# Maker_Display2.net
KiCad netlist of a schematic drawn in EAGLE
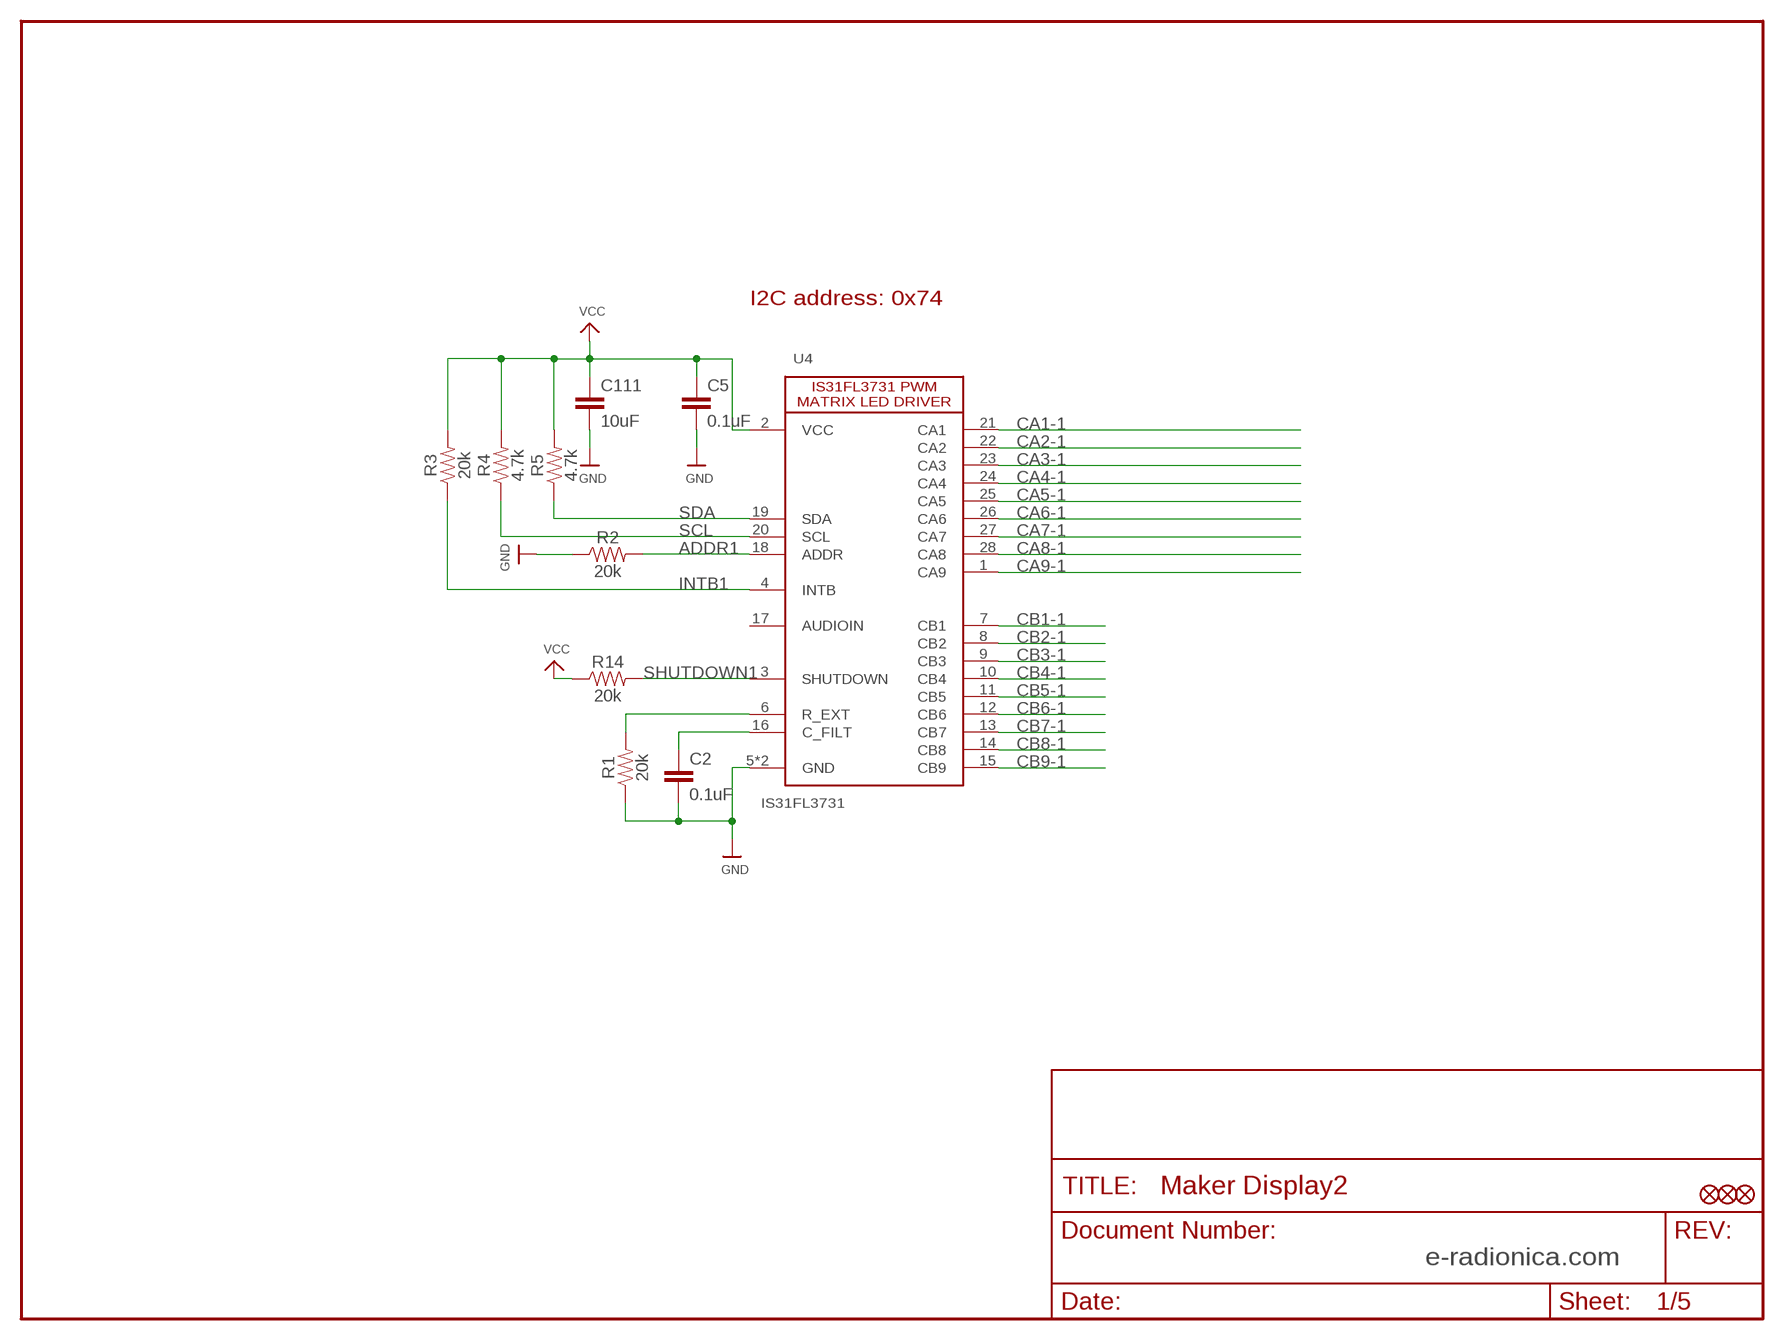
[diagram p0: schematic, sheet 1]
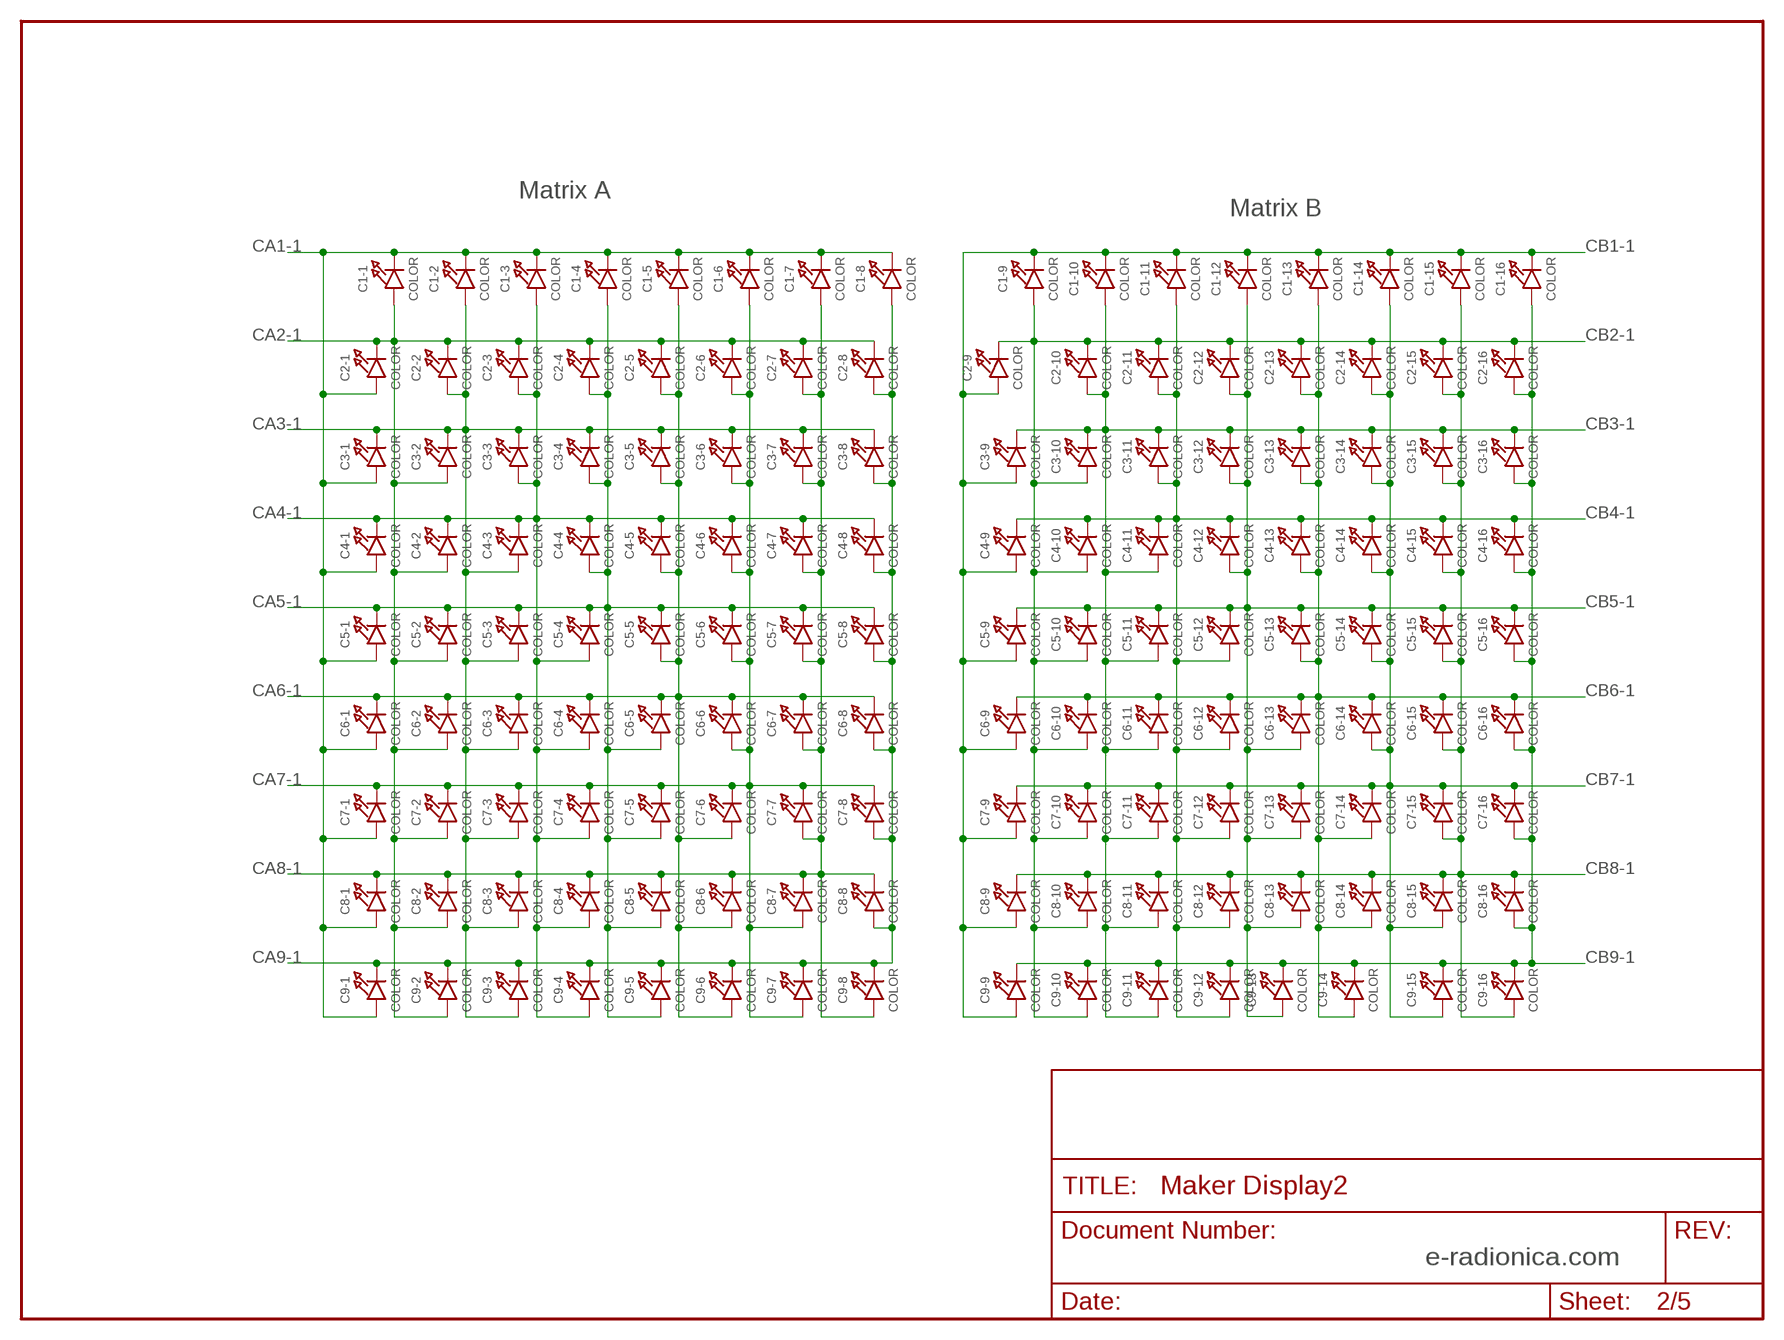
[diagram p1: schematic, sheet 2]
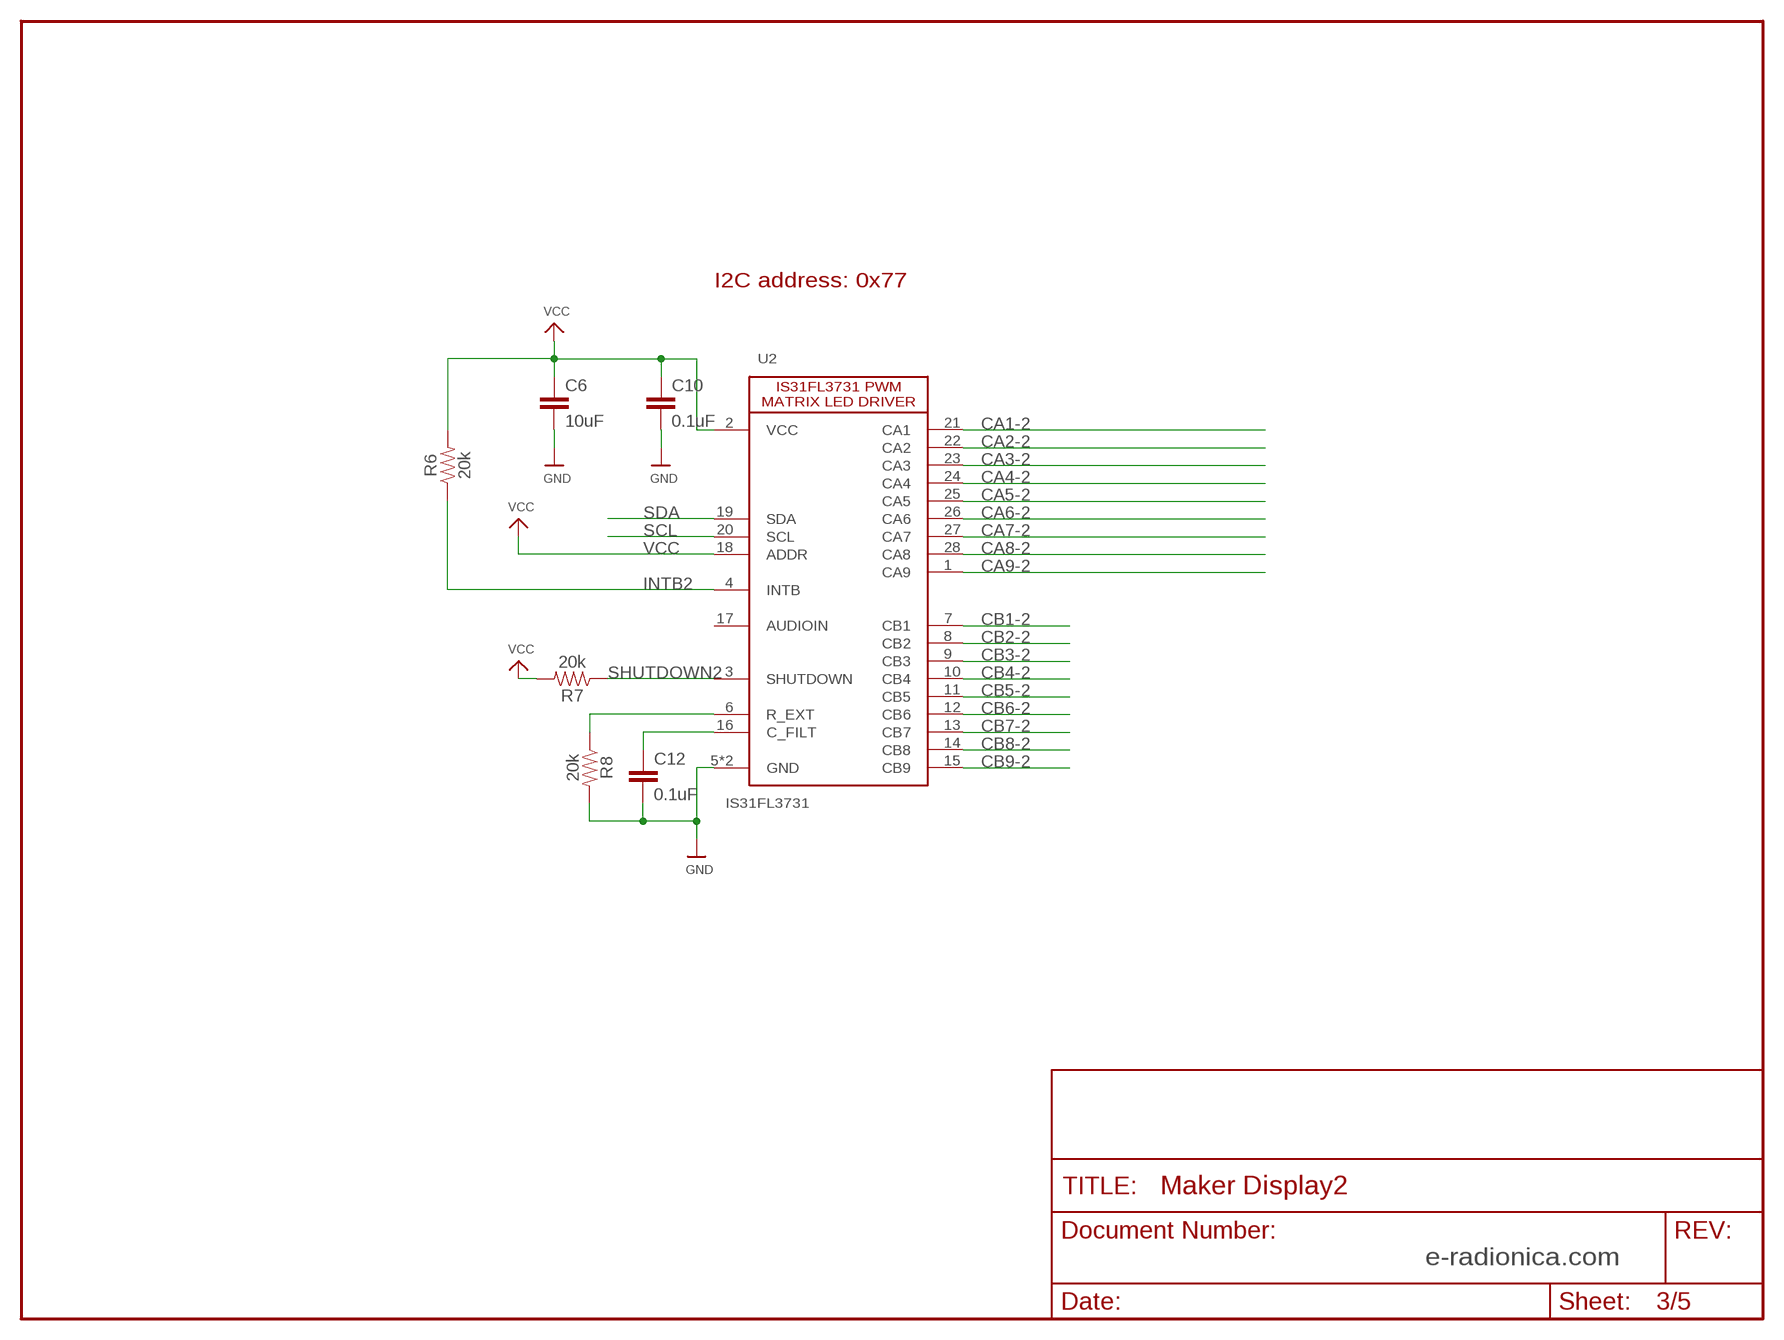
[diagram p2: schematic, sheet 3]
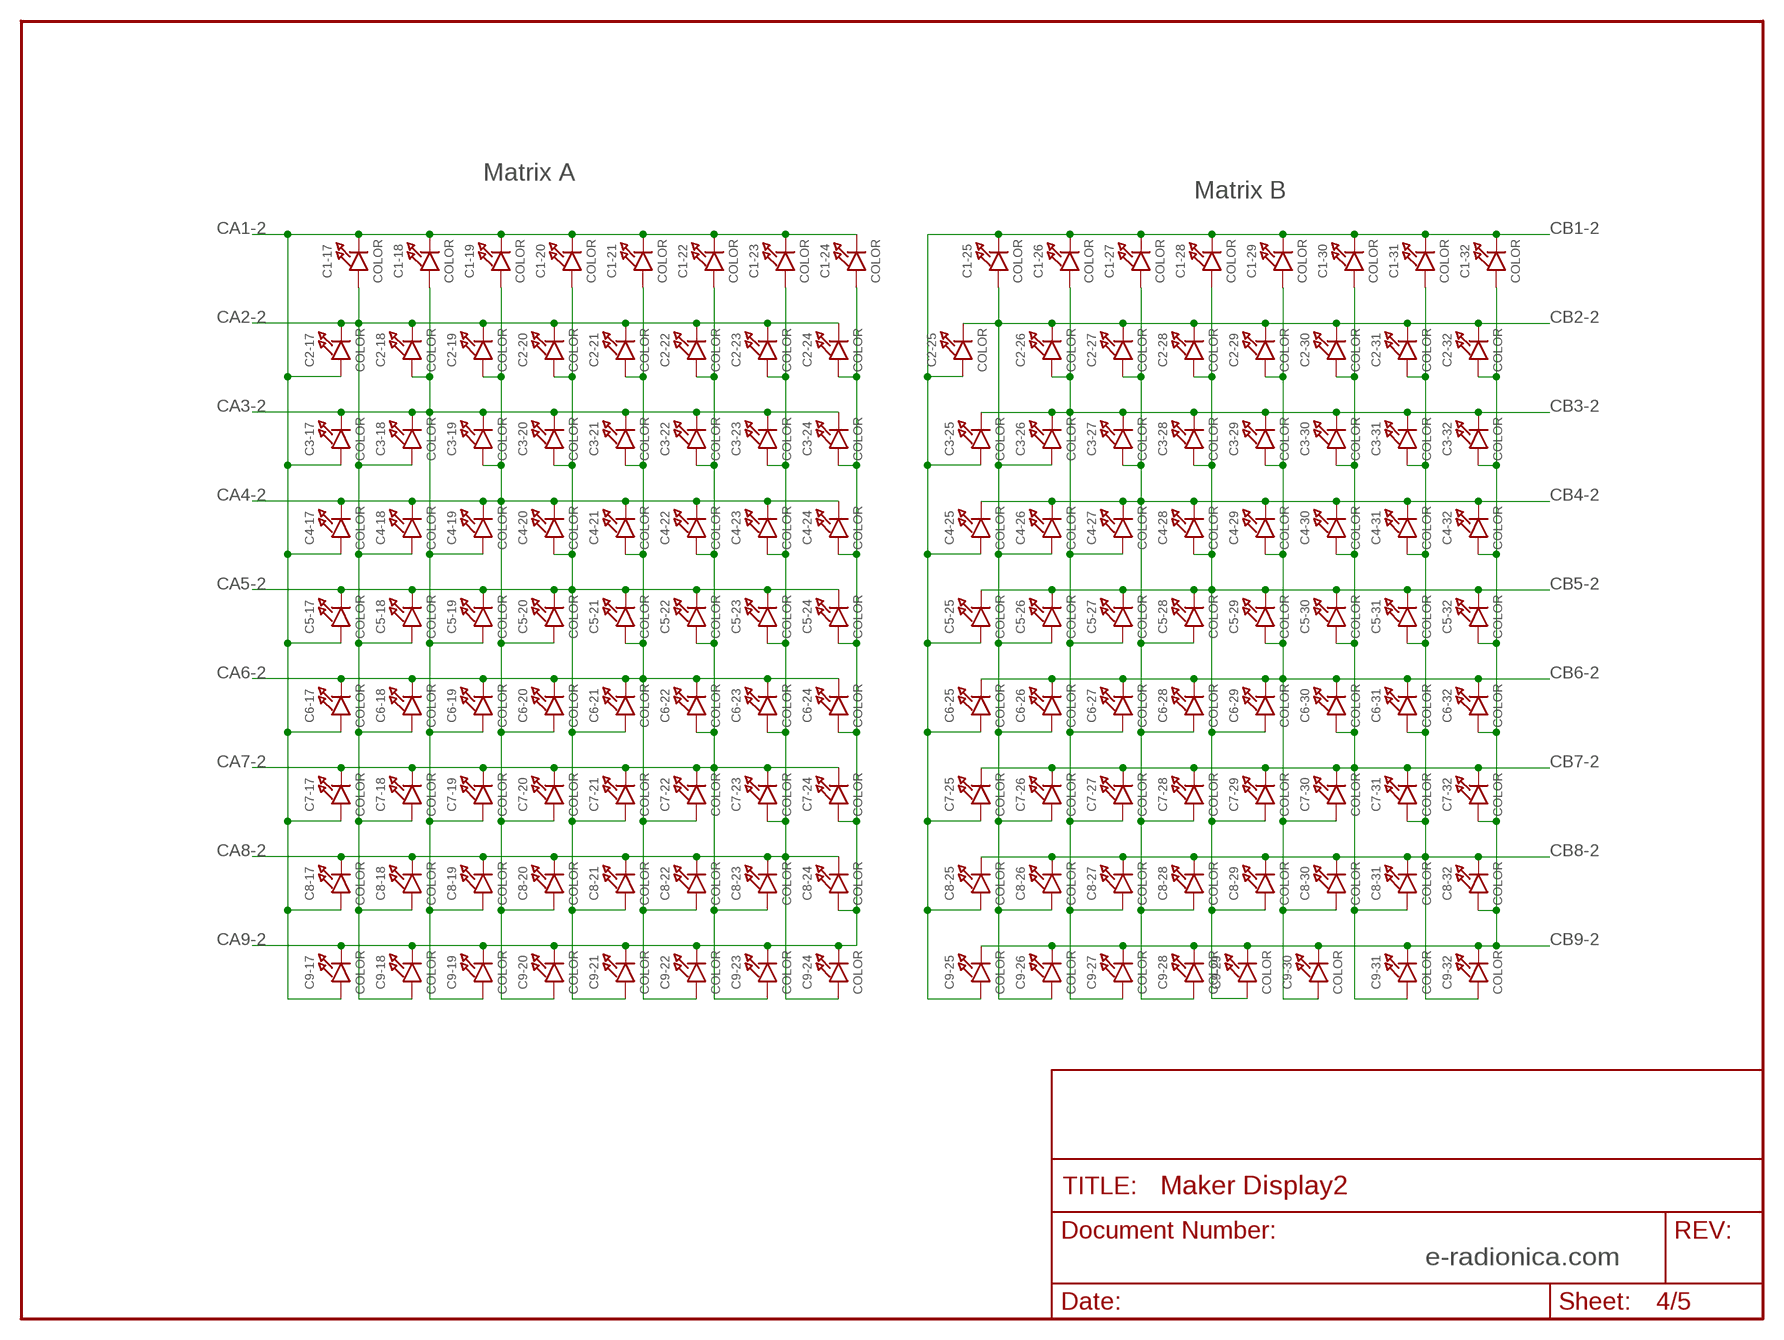
[diagram p3: schematic, sheet 4]
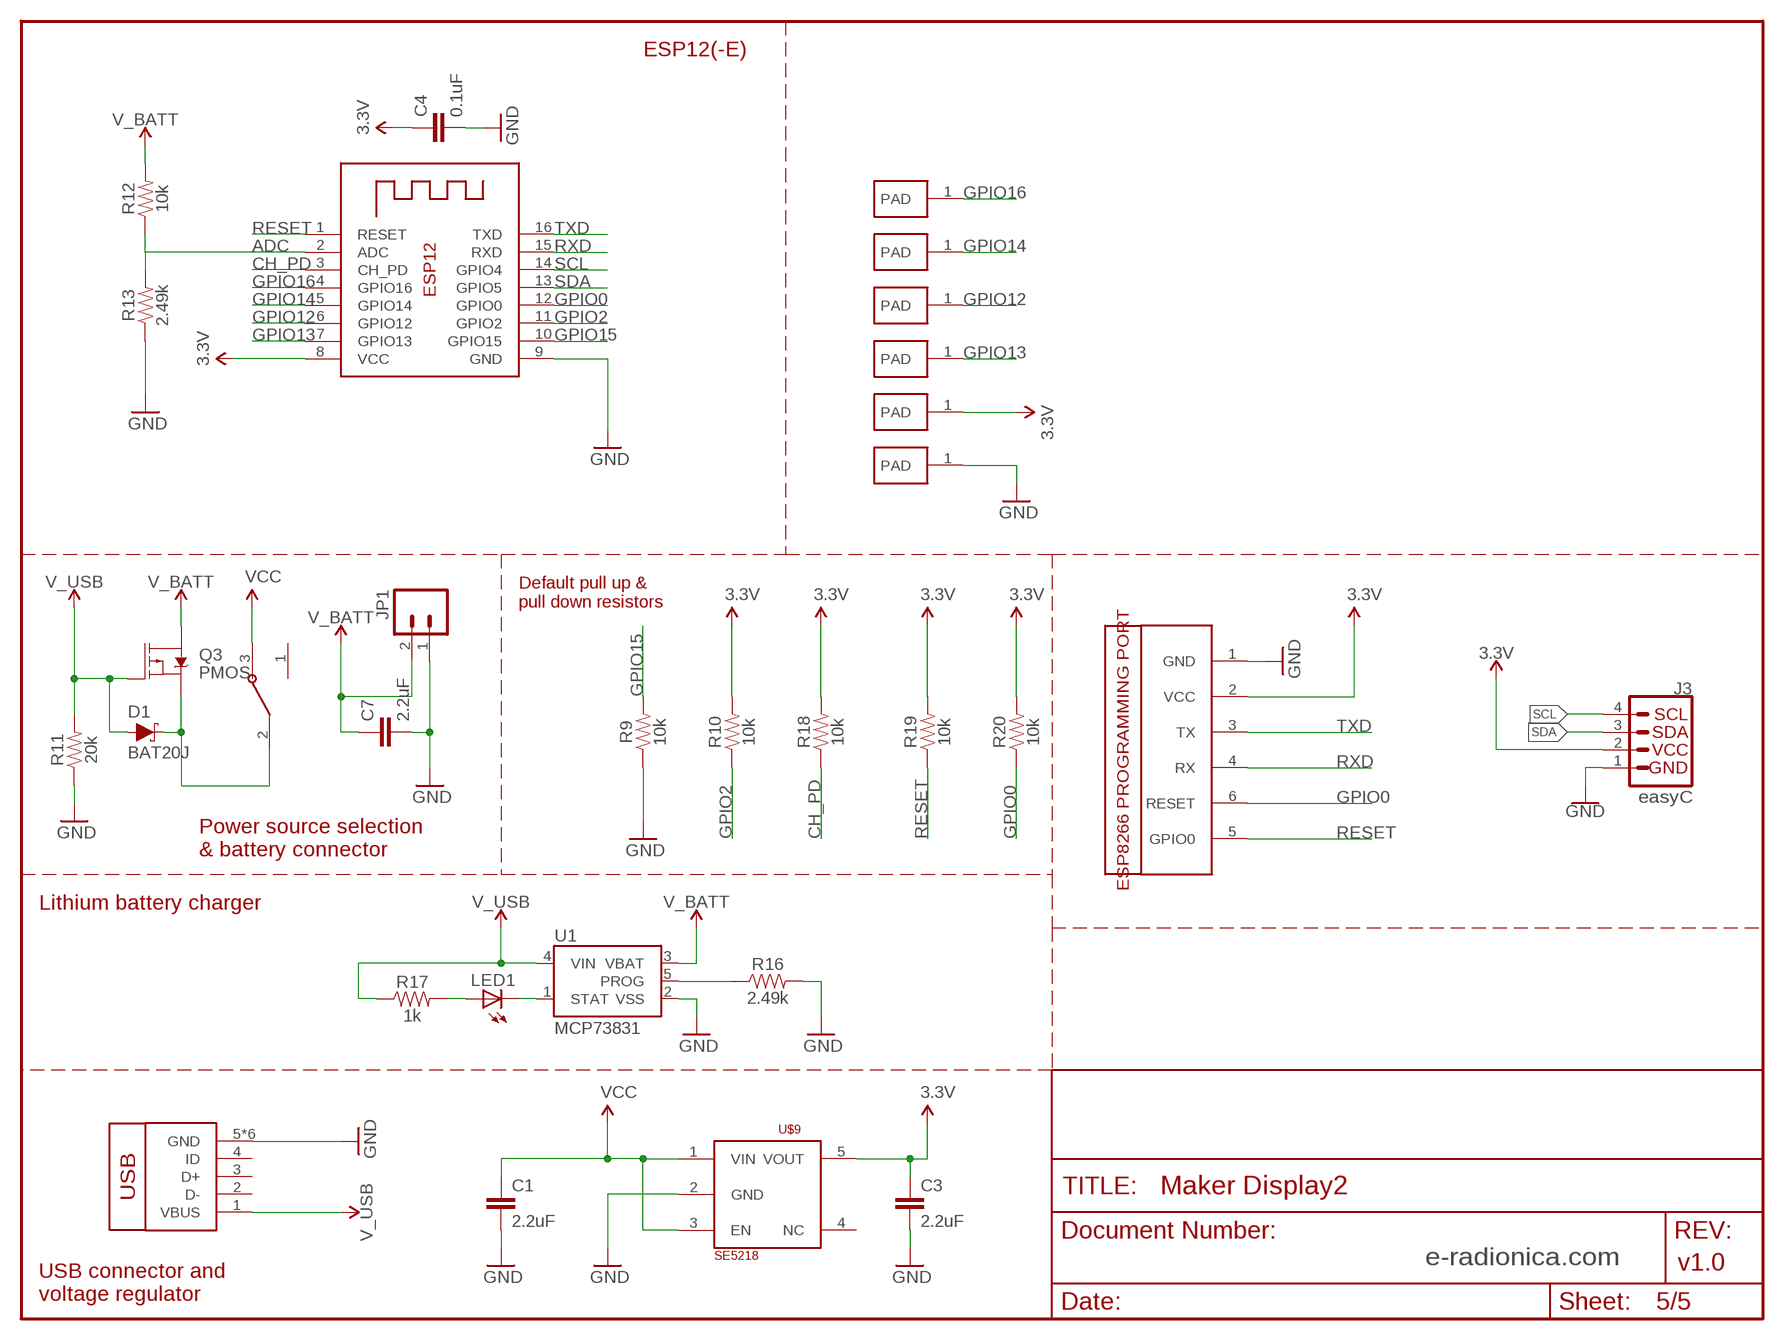
[diagram p4: schematic, sheet 5]

(export (version "E")
  (design (tool "Eeschema 10.0.6"))
  (components
    (comp (ref "C1")
      (value "2.2uF")
      (footprint "eagle-import:0603")
      (libsource (lib "eagle-import") (part "2.2UF-0603-10V-20%"))
    )
    (comp (ref "C3")
      (value "2.2uF")
      (footprint "eagle-import:0603")
      (libsource (lib "eagle-import") (part "2.2UF-0603-10V-20%"))
    )
    (comp (ref "C4")
      (value "0.1uF")
      (footprint "eagle-import:0603")
      (libsource (lib "eagle-import") (part "0.1UF-0603-25V-(+80/-20%)"))
    )
    (comp (ref "C7")
      (value "2.2uF")
      (footprint "eagle-import:0603")
      (libsource (lib "eagle-import") (part "2.2UF-0603-10V-20%"))
    )
    (comp (ref "D1")
      (value "BAT20J")
      (footprint "eagle-import:SOD-323")
      (libsource (lib "eagle-import") (part "DIODE-SCHOTTKY-BAT20J"))
    )
    (comp (ref "J3")
      (value "QWIIC_CONNECTORJS-1MM")
      (footprint "eagle-import:1X04_1MM_RA")
      (libsource (lib "eagle-import") (part "QWIIC_CONNECTORJS-1MM"))
    )
    (comp (ref "JP1")
      (value "M02-JST-2MM-SMT")
      (footprint "eagle-import:JST-2-SMD")
      (libsource (lib "eagle-import") (part "M02-JST-2MM-SMT"))
    )
    (comp (ref "LED1")
      (value "LEDCHIPLED_0805")
      (footprint "eagle-import:CHIPLED_0805")
      (libsource (lib "eagle-import") (part "LEDCHIPLED_0805"))
    )
    (comp (ref "Q3")
      (value "PMOS")
      (footprint "eagle-import:SOT23-3")
      (libsource (lib "eagle-import") (part "MOSFET_PCH-DMG2307L"))
    )
    (comp (ref "R9")
      (value "10k")
      (footprint "eagle-import:0603")
      (libsource (lib "eagle-import") (part "10KOHM-0603-1/10W-1%"))
    )
    (comp (ref "R10")
      (value "10k")
      (footprint "eagle-import:0603")
      (libsource (lib "eagle-import") (part "10KOHM-0603-1/10W-1%"))
    )
    (comp (ref "R11")
      (value "20k")
      (footprint "eagle-import:0603")
      (libsource (lib "eagle-import") (part "20KOHM-0603-1/10W-1%"))
    )
    (comp (ref "R12")
      (value "10k")
      (footprint "eagle-import:0603")
      (libsource (lib "eagle-import") (part "10KOHM-0603-1/10W-1%"))
    )
    (comp (ref "R13")
      (value "2.49k")
      (footprint "eagle-import:0603")
      (libsource (lib "eagle-import") (part "2.49KOHM-0603-1/10W-1%"))
    )
    (comp (ref "R16")
      (value "2.49k")
      (footprint "eagle-import:0603")
      (libsource (lib "eagle-import") (part "2.49KOHM-0603-1/10W-1%"))
    )
    (comp (ref "R17")
      (value "1k")
      (footprint "eagle-import:0603")
      (libsource (lib "eagle-import") (part "1KOHM-0603-1/10W-1%"))
    )
    (comp (ref "R18")
      (value "10k")
      (footprint "eagle-import:0603")
      (libsource (lib "eagle-import") (part "10KOHM-0603-1/10W-1%"))
    )
    (comp (ref "R19")
      (value "10k")
      (footprint "eagle-import:0603")
      (libsource (lib "eagle-import") (part "10KOHM-0603-1/10W-1%"))
    )
    (comp (ref "R20")
      (value "10k")
      (footprint "eagle-import:0603")
      (libsource (lib "eagle-import") (part "10KOHM-0603-1/10W-1%"))
    )
    (comp (ref "S1")
      (value "SWITCH_SK-12D02-VG5")
      (footprint "eagle-import:SK-12D02-VG5")
      (libsource (lib "eagle-import") (part "SWITCH_SK-12D02-VG5"))
    )
    (comp (ref "U$3")
      (value "ESP-PROGRAMMINGPORT")
      (footprint "eagle-import:ESP-PROGRAMMING-PORT")
      (libsource (lib "eagle-import") (part "ESP-PROGRAMMINGPORT"))
    )
    (comp (ref "U$4")
      (value "PAD-1")
      (footprint "eagle-import:PAD-1")
      (libsource (lib "eagle-import") (part "PAD-1"))
    )
    (comp (ref "U$5")
      (value "PAD-1")
      (footprint "eagle-import:PAD-1")
      (libsource (lib "eagle-import") (part "PAD-1"))
    )
    (comp (ref "U$6")
      (value "PAD-1")
      (footprint "eagle-import:PAD-1")
      (libsource (lib "eagle-import") (part "PAD-1"))
    )
    (comp (ref "U$7")
      (value "PAD-1")
      (footprint "eagle-import:PAD-1")
      (libsource (lib "eagle-import") (part "PAD-1"))
    )
    (comp (ref "U$9")
      (value "SE5218")
      (footprint "eagle-import:SOT23-5")
      (libsource (lib "eagle-import") (part "SE5218"))
    )
    (comp (ref "U$12")
      (value "PAD-1")
      (footprint "eagle-import:PAD-1")
      (libsource (lib "eagle-import") (part "PAD-1"))
    )
    (comp (ref "U$14")
      (value "PAD-1")
      (footprint "eagle-import:PAD-1")
      (libsource (lib "eagle-import") (part "PAD-1"))
    )
    (comp (ref "U$15")
      (value "USB-MICRO")
      (footprint "eagle-import:U-F-M5DD-Y-L")
      (libsource (lib "eagle-import") (part "USB-MICRO"))
    )
    (comp (ref "U1")
      (value "MCP73831")
      (footprint "eagle-import:SOT23-5")
      (libsource (lib "eagle-import") (part "MCP73831"))
    )
    (comp (ref "X1")
      (value "ESP8266-12")
      (footprint "eagle-import:ESP-12")
      (libsource (lib "eagle-import") (part "ESP-12"))
    )
    (comp (ref "C1-17")
      (value "COLOR")
      (footprint "eagle-import:CHIPLED_0603_NOOUTLINE")
      (libsource (lib "eagle-import") (part "LED0603_NOOUTLINE"))
    )
    (comp (ref "C1-18")
      (value "COLOR")
      (footprint "eagle-import:CHIPLED_0603_NOOUTLINE")
      (libsource (lib "eagle-import") (part "LED0603_NOOUTLINE"))
    )
    (comp (ref "C1-19")
      (value "COLOR")
      (footprint "eagle-import:CHIPLED_0603_NOOUTLINE")
      (libsource (lib "eagle-import") (part "LED0603_NOOUTLINE"))
    )
    (comp (ref "C1-20")
      (value "COLOR")
      (footprint "eagle-import:CHIPLED_0603_NOOUTLINE")
      (libsource (lib "eagle-import") (part "LED0603_NOOUTLINE"))
    )
    (comp (ref "C1-21")
      (value "COLOR")
      (footprint "eagle-import:CHIPLED_0603_NOOUTLINE")
      (libsource (lib "eagle-import") (part "LED0603_NOOUTLINE"))
    )
    (comp (ref "C1-22")
      (value "COLOR")
      (footprint "eagle-import:CHIPLED_0603_NOOUTLINE")
      (libsource (lib "eagle-import") (part "LED0603_NOOUTLINE"))
    )
    (comp (ref "C1-23")
      (value "COLOR")
      (footprint "eagle-import:CHIPLED_0603_NOOUTLINE")
      (libsource (lib "eagle-import") (part "LED0603_NOOUTLINE"))
    )
    (comp (ref "C1-24")
      (value "COLOR")
      (footprint "eagle-import:CHIPLED_0603_NOOUTLINE")
      (libsource (lib "eagle-import") (part "LED0603_NOOUTLINE"))
    )
    (comp (ref "C1-25")
      (value "COLOR")
      (footprint "eagle-import:CHIPLED_0603_NOOUTLINE")
      (libsource (lib "eagle-import") (part "LED0603_NOOUTLINE"))
    )
    (comp (ref "C1-26")
      (value "COLOR")
      (footprint "eagle-import:CHIPLED_0603_NOOUTLINE")
      (libsource (lib "eagle-import") (part "LED0603_NOOUTLINE"))
    )
    (comp (ref "C1-27")
      (value "COLOR")
      (footprint "eagle-import:CHIPLED_0603_NOOUTLINE")
      (libsource (lib "eagle-import") (part "LED0603_NOOUTLINE"))
    )
    (comp (ref "C1-28")
      (value "COLOR")
      (footprint "eagle-import:CHIPLED_0603_NOOUTLINE")
      (libsource (lib "eagle-import") (part "LED0603_NOOUTLINE"))
    )
    (comp (ref "C1-29")
      (value "COLOR")
      (footprint "eagle-import:CHIPLED_0603_NOOUTLINE")
      (libsource (lib "eagle-import") (part "LED0603_NOOUTLINE"))
    )
    (comp (ref "C1-30")
      (value "COLOR")
      (footprint "eagle-import:CHIPLED_0603_NOOUTLINE")
      (libsource (lib "eagle-import") (part "LED0603_NOOUTLINE"))
    )
    (comp (ref "C1-31")
      (value "COLOR")
      (footprint "eagle-import:CHIPLED_0603_NOOUTLINE")
      (libsource (lib "eagle-import") (part "LED0603_NOOUTLINE"))
    )
    (comp (ref "C1-32")
      (value "COLOR")
      (footprint "eagle-import:CHIPLED_0603_NOOUTLINE")
      (libsource (lib "eagle-import") (part "LED0603_NOOUTLINE"))
    )
    (comp (ref "C2-17")
      (value "COLOR")
      (footprint "eagle-import:CHIPLED_0603_NOOUTLINE")
      (libsource (lib "eagle-import") (part "LED0603_NOOUTLINE"))
    )
    (comp (ref "C2-18")
      (value "COLOR")
      (footprint "eagle-import:CHIPLED_0603_NOOUTLINE")
      (libsource (lib "eagle-import") (part "LED0603_NOOUTLINE"))
    )
    (comp (ref "C2-19")
      (value "COLOR")
      (footprint "eagle-import:CHIPLED_0603_NOOUTLINE")
      (libsource (lib "eagle-import") (part "LED0603_NOOUTLINE"))
    )
    (comp (ref "C2-20")
      (value "COLOR")
      (footprint "eagle-import:CHIPLED_0603_NOOUTLINE")
      (libsource (lib "eagle-import") (part "LED0603_NOOUTLINE"))
    )
    (comp (ref "C2-21")
      (value "COLOR")
      (footprint "eagle-import:CHIPLED_0603_NOOUTLINE")
      (libsource (lib "eagle-import") (part "LED0603_NOOUTLINE"))
    )
    (comp (ref "C2-22")
      (value "COLOR")
      (footprint "eagle-import:CHIPLED_0603_NOOUTLINE")
      (libsource (lib "eagle-import") (part "LED0603_NOOUTLINE"))
    )
    (comp (ref "C2-23")
      (value "COLOR")
      (footprint "eagle-import:CHIPLED_0603_NOOUTLINE")
      (libsource (lib "eagle-import") (part "LED0603_NOOUTLINE"))
    )
    (comp (ref "C2-24")
      (value "COLOR")
      (footprint "eagle-import:CHIPLED_0603_NOOUTLINE")
      (libsource (lib "eagle-import") (part "LED0603_NOOUTLINE"))
    )
    (comp (ref "C2-25")
      (value "COLOR")
      (footprint "eagle-import:CHIPLED_0603_NOOUTLINE")
      (libsource (lib "eagle-import") (part "LED0603_NOOUTLINE"))
    )
    (comp (ref "C2-26")
      (value "COLOR")
      (footprint "eagle-import:CHIPLED_0603_NOOUTLINE")
      (libsource (lib "eagle-import") (part "LED0603_NOOUTLINE"))
    )
    (comp (ref "C2-27")
      (value "COLOR")
      (footprint "eagle-import:CHIPLED_0603_NOOUTLINE")
      (libsource (lib "eagle-import") (part "LED0603_NOOUTLINE"))
    )
    (comp (ref "C2-28")
      (value "COLOR")
      (footprint "eagle-import:CHIPLED_0603_NOOUTLINE")
      (libsource (lib "eagle-import") (part "LED0603_NOOUTLINE"))
    )
    (comp (ref "C2-29")
      (value "COLOR")
      (footprint "eagle-import:CHIPLED_0603_NOOUTLINE")
      (libsource (lib "eagle-import") (part "LED0603_NOOUTLINE"))
    )
    (comp (ref "C2-30")
      (value "COLOR")
      (footprint "eagle-import:CHIPLED_0603_NOOUTLINE")
      (libsource (lib "eagle-import") (part "LED0603_NOOUTLINE"))
    )
    (comp (ref "C2-31")
      (value "COLOR")
      (footprint "eagle-import:CHIPLED_0603_NOOUTLINE")
      (libsource (lib "eagle-import") (part "LED0603_NOOUTLINE"))
    )
    (comp (ref "C2-32")
      (value "COLOR")
      (footprint "eagle-import:CHIPLED_0603_NOOUTLINE")
      (libsource (lib "eagle-import") (part "LED0603_NOOUTLINE"))
    )
    (comp (ref "C3-17")
      (value "COLOR")
      (footprint "eagle-import:CHIPLED_0603_NOOUTLINE")
      (libsource (lib "eagle-import") (part "LED0603_NOOUTLINE"))
    )
    (comp (ref "C3-18")
      (value "COLOR")
      (footprint "eagle-import:CHIPLED_0603_NOOUTLINE")
      (libsource (lib "eagle-import") (part "LED0603_NOOUTLINE"))
    )
    (comp (ref "C3-19")
      (value "COLOR")
      (footprint "eagle-import:CHIPLED_0603_NOOUTLINE")
      (libsource (lib "eagle-import") (part "LED0603_NOOUTLINE"))
    )
    (comp (ref "C3-20")
      (value "COLOR")
      (footprint "eagle-import:CHIPLED_0603_NOOUTLINE")
      (libsource (lib "eagle-import") (part "LED0603_NOOUTLINE"))
    )
    (comp (ref "C3-21")
      (value "COLOR")
      (footprint "eagle-import:CHIPLED_0603_NOOUTLINE")
      (libsource (lib "eagle-import") (part "LED0603_NOOUTLINE"))
    )
    (comp (ref "C3-22")
      (value "COLOR")
      (footprint "eagle-import:CHIPLED_0603_NOOUTLINE")
      (libsource (lib "eagle-import") (part "LED0603_NOOUTLINE"))
    )
    (comp (ref "C3-23")
      (value "COLOR")
      (footprint "eagle-import:CHIPLED_0603_NOOUTLINE")
      (libsource (lib "eagle-import") (part "LED0603_NOOUTLINE"))
    )
    (comp (ref "C3-24")
      (value "COLOR")
      (footprint "eagle-import:CHIPLED_0603_NOOUTLINE")
      (libsource (lib "eagle-import") (part "LED0603_NOOUTLINE"))
    )
    (comp (ref "C3-25")
      (value "COLOR")
      (footprint "eagle-import:CHIPLED_0603_NOOUTLINE")
      (libsource (lib "eagle-import") (part "LED0603_NOOUTLINE"))
    )
    (comp (ref "C3-26")
      (value "COLOR")
      (footprint "eagle-import:CHIPLED_0603_NOOUTLINE")
      (libsource (lib "eagle-import") (part "LED0603_NOOUTLINE"))
    )
    (comp (ref "C3-27")
      (value "COLOR")
      (footprint "eagle-import:CHIPLED_0603_NOOUTLINE")
      (libsource (lib "eagle-import") (part "LED0603_NOOUTLINE"))
    )
    (comp (ref "C3-28")
      (value "COLOR")
      (footprint "eagle-import:CHIPLED_0603_NOOUTLINE")
      (libsource (lib "eagle-import") (part "LED0603_NOOUTLINE"))
    )
    (comp (ref "C3-29")
      (value "COLOR")
      (footprint "eagle-import:CHIPLED_0603_NOOUTLINE")
      (libsource (lib "eagle-import") (part "LED0603_NOOUTLINE"))
    )
    (comp (ref "C3-30")
      (value "COLOR")
      (footprint "eagle-import:CHIPLED_0603_NOOUTLINE")
      (libsource (lib "eagle-import") (part "LED0603_NOOUTLINE"))
    )
    (comp (ref "C3-31")
      (value "COLOR")
      (footprint "eagle-import:CHIPLED_0603_NOOUTLINE")
      (libsource (lib "eagle-import") (part "LED0603_NOOUTLINE"))
    )
    (comp (ref "C3-32")
      (value "COLOR")
      (footprint "eagle-import:CHIPLED_0603_NOOUTLINE")
      (libsource (lib "eagle-import") (part "LED0603_NOOUTLINE"))
    )
    (comp (ref "C4-17")
      (value "COLOR")
      (footprint "eagle-import:CHIPLED_0603_NOOUTLINE")
      (libsource (lib "eagle-import") (part "LED0603_NOOUTLINE"))
    )
    (comp (ref "C4-18")
      (value "COLOR")
      (footprint "eagle-import:CHIPLED_0603_NOOUTLINE")
      (libsource (lib "eagle-import") (part "LED0603_NOOUTLINE"))
    )
    (comp (ref "C4-19")
      (value "COLOR")
      (footprint "eagle-import:CHIPLED_0603_NOOUTLINE")
      (libsource (lib "eagle-import") (part "LED0603_NOOUTLINE"))
    )
    (comp (ref "C4-20")
      (value "COLOR")
      (footprint "eagle-import:CHIPLED_0603_NOOUTLINE")
      (libsource (lib "eagle-import") (part "LED0603_NOOUTLINE"))
    )
    (comp (ref "C4-21")
      (value "COLOR")
      (footprint "eagle-import:CHIPLED_0603_NOOUTLINE")
      (libsource (lib "eagle-import") (part "LED0603_NOOUTLINE"))
    )
    (comp (ref "C4-22")
      (value "COLOR")
      (footprint "eagle-import:CHIPLED_0603_NOOUTLINE")
      (libsource (lib "eagle-import") (part "LED0603_NOOUTLINE"))
    )
    (comp (ref "C4-23")
      (value "COLOR")
      (footprint "eagle-import:CHIPLED_0603_NOOUTLINE")
      (libsource (lib "eagle-import") (part "LED0603_NOOUTLINE"))
    )
    (comp (ref "C4-24")
      (value "COLOR")
      (footprint "eagle-import:CHIPLED_0603_NOOUTLINE")
      (libsource (lib "eagle-import") (part "LED0603_NOOUTLINE"))
    )
    (comp (ref "C4-25")
      (value "COLOR")
      (footprint "eagle-import:CHIPLED_0603_NOOUTLINE")
      (libsource (lib "eagle-import") (part "LED0603_NOOUTLINE"))
    )
    (comp (ref "C4-26")
      (value "COLOR")
      (footprint "eagle-import:CHIPLED_0603_NOOUTLINE")
      (libsource (lib "eagle-import") (part "LED0603_NOOUTLINE"))
    )
    (comp (ref "C4-27")
      (value "COLOR")
      (footprint "eagle-import:CHIPLED_0603_NOOUTLINE")
      (libsource (lib "eagle-import") (part "LED0603_NOOUTLINE"))
    )
    (comp (ref "C4-28")
      (value "COLOR")
      (footprint "eagle-import:CHIPLED_0603_NOOUTLINE")
      (libsource (lib "eagle-import") (part "LED0603_NOOUTLINE"))
    )
    (comp (ref "C4-29")
      (value "COLOR")
      (footprint "eagle-import:CHIPLED_0603_NOOUTLINE")
      (libsource (lib "eagle-import") (part "LED0603_NOOUTLINE"))
    )
    (comp (ref "C4-30")
      (value "COLOR")
      (footprint "eagle-import:CHIPLED_0603_NOOUTLINE")
      (libsource (lib "eagle-import") (part "LED0603_NOOUTLINE"))
    )
    (comp (ref "C4-31")
      (value "COLOR")
      (footprint "eagle-import:CHIPLED_0603_NOOUTLINE")
      (libsource (lib "eagle-import") (part "LED0603_NOOUTLINE"))
    )
    (comp (ref "C4-32")
      (value "COLOR")
      (footprint "eagle-import:CHIPLED_0603_NOOUTLINE")
      (libsource (lib "eagle-import") (part "LED0603_NOOUTLINE"))
    )
    (comp (ref "C5-17")
      (value "COLOR")
      (footprint "eagle-import:CHIPLED_0603_NOOUTLINE")
      (libsource (lib "eagle-import") (part "LED0603_NOOUTLINE"))
    )
    (comp (ref "C5-18")
      (value "COLOR")
      (footprint "eagle-import:CHIPLED_0603_NOOUTLINE")
      (libsource (lib "eagle-import") (part "LED0603_NOOUTLINE"))
    )
    (comp (ref "C5-19")
      (value "COLOR")
      (footprint "eagle-import:CHIPLED_0603_NOOUTLINE")
      (libsource (lib "eagle-import") (part "LED0603_NOOUTLINE"))
    )
    (comp (ref "C5-20")
      (value "COLOR")
      (footprint "eagle-import:CHIPLED_0603_NOOUTLINE")
      (libsource (lib "eagle-import") (part "LED0603_NOOUTLINE"))
    )
    (comp (ref "C5-21")
      (value "COLOR")
      (footprint "eagle-import:CHIPLED_0603_NOOUTLINE")
      (libsource (lib "eagle-import") (part "LED0603_NOOUTLINE"))
    )
    (comp (ref "C5-22")
      (value "COLOR")
      (footprint "eagle-import:CHIPLED_0603_NOOUTLINE")
      (libsource (lib "eagle-import") (part "LED0603_NOOUTLINE"))
    )
    (comp (ref "C5-23")
      (value "COLOR")
      (footprint "eagle-import:CHIPLED_0603_NOOUTLINE")
      (libsource (lib "eagle-import") (part "LED0603_NOOUTLINE"))
    )
    (comp (ref "C5-24")
      (value "COLOR")
      (footprint "eagle-import:CHIPLED_0603_NOOUTLINE")
      (libsource (lib "eagle-import") (part "LED0603_NOOUTLINE"))
    )
    (comp (ref "C5-25")
      (value "COLOR")
      (footprint "eagle-import:CHIPLED_0603_NOOUTLINE")
      (libsource (lib "eagle-import") (part "LED0603_NOOUTLINE"))
    )
    (comp (ref "C5-26")
      (value "COLOR")
      (footprint "eagle-import:CHIPLED_0603_NOOUTLINE")
      (libsource (lib "eagle-import") (part "LED0603_NOOUTLINE"))
    )
    (comp (ref "C5-27")
      (value "COLOR")
      (footprint "eagle-import:CHIPLED_0603_NOOUTLINE")
      (libsource (lib "eagle-import") (part "LED0603_NOOUTLINE"))
    )
    (comp (ref "C5-28")
      (value "COLOR")
      (footprint "eagle-import:CHIPLED_0603_NOOUTLINE")
      (libsource (lib "eagle-import") (part "LED0603_NOOUTLINE"))
    )
    (comp (ref "C5-29")
      (value "COLOR")
      (footprint "eagle-import:CHIPLED_0603_NOOUTLINE")
      (libsource (lib "eagle-import") (part "LED0603_NOOUTLINE"))
    )
    (comp (ref "C5-30")
      (value "COLOR")
      (footprint "eagle-import:CHIPLED_0603_NOOUTLINE")
      (libsource (lib "eagle-import") (part "LED0603_NOOUTLINE"))
    )
    (comp (ref "C5-31")
      (value "COLOR")
      (footprint "eagle-import:CHIPLED_0603_NOOUTLINE")
      (libsource (lib "eagle-import") (part "LED0603_NOOUTLINE"))
    )
    (comp (ref "C5-32")
      (value "COLOR")
      (footprint "eagle-import:CHIPLED_0603_NOOUTLINE")
      (libsource (lib "eagle-import") (part "LED0603_NOOUTLINE"))
    )
    (comp (ref "C6-17")
      (value "COLOR")
      (footprint "eagle-import:CHIPLED_0603_NOOUTLINE")
      (libsource (lib "eagle-import") (part "LED0603_NOOUTLINE"))
    )
    (comp (ref "C6-18")
      (value "COLOR")
      (footprint "eagle-import:CHIPLED_0603_NOOUTLINE")
      (libsource (lib "eagle-import") (part "LED0603_NOOUTLINE"))
    )
    (comp (ref "C6-19")
      (value "COLOR")
      (footprint "eagle-import:CHIPLED_0603_NOOUTLINE")
      (libsource (lib "eagle-import") (part "LED0603_NOOUTLINE"))
    )
    (comp (ref "C6-20")
      (value "COLOR")
      (footprint "eagle-import:CHIPLED_0603_NOOUTLINE")
      (libsource (lib "eagle-import") (part "LED0603_NOOUTLINE"))
    )
    (comp (ref "C6-21")
      (value "COLOR")
      (footprint "eagle-import:CHIPLED_0603_NOOUTLINE")
      (libsource (lib "eagle-import") (part "LED0603_NOOUTLINE"))
    )
    (comp (ref "C6-22")
      (value "COLOR")
      (footprint "eagle-import:CHIPLED_0603_NOOUTLINE")
      (libsource (lib "eagle-import") (part "LED0603_NOOUTLINE"))
    )
    (comp (ref "C6-23")
      (value "COLOR")
      (footprint "eagle-import:CHIPLED_0603_NOOUTLINE")
      (libsource (lib "eagle-import") (part "LED0603_NOOUTLINE"))
    )
    (comp (ref "C6-24")
      (value "COLOR")
      (footprint "eagle-import:CHIPLED_0603_NOOUTLINE")
      (libsource (lib "eagle-import") (part "LED0603_NOOUTLINE"))
    )
    (comp (ref "C6-25")
      (value "COLOR")
      (footprint "eagle-import:CHIPLED_0603_NOOUTLINE")
      (libsource (lib "eagle-import") (part "LED0603_NOOUTLINE"))
    )
    (comp (ref "C6-26")
      (value "COLOR")
      (footprint "eagle-import:CHIPLED_0603_NOOUTLINE")
      (libsource (lib "eagle-import") (part "LED0603_NOOUTLINE"))
    )
    (comp (ref "C6-27")
      (value "COLOR")
      (footprint "eagle-import:CHIPLED_0603_NOOUTLINE")
      (libsource (lib "eagle-import") (part "LED0603_NOOUTLINE"))
    )
    (comp (ref "C6-28")
      (value "COLOR")
      (footprint "eagle-import:CHIPLED_0603_NOOUTLINE")
      (libsource (lib "eagle-import") (part "LED0603_NOOUTLINE"))
    )
    (comp (ref "C6-29")
      (value "COLOR")
      (footprint "eagle-import:CHIPLED_0603_NOOUTLINE")
      (libsource (lib "eagle-import") (part "LED0603_NOOUTLINE"))
    )
    (comp (ref "C6-30")
      (value "COLOR")
      (footprint "eagle-import:CHIPLED_0603_NOOUTLINE")
      (libsource (lib "eagle-import") (part "LED0603_NOOUTLINE"))
    )
    (comp (ref "C6-31")
      (value "COLOR")
      (footprint "eagle-import:CHIPLED_0603_NOOUTLINE")
      (libsource (lib "eagle-import") (part "LED0603_NOOUTLINE"))
    )
    (comp (ref "C6-32")
      (value "COLOR")
      (footprint "eagle-import:CHIPLED_0603_NOOUTLINE")
      (libsource (lib "eagle-import") (part "LED0603_NOOUTLINE"))
    )
    (comp (ref "C7-17")
      (value "COLOR")
      (footprint "eagle-import:CHIPLED_0603_NOOUTLINE")
      (libsource (lib "eagle-import") (part "LED0603_NOOUTLINE"))
    )
    (comp (ref "C7-18")
      (value "COLOR")
      (footprint "eagle-import:CHIPLED_0603_NOOUTLINE")
      (libsource (lib "eagle-import") (part "LED0603_NOOUTLINE"))
    )
    (comp (ref "C7-19")
      (value "COLOR")
      (footprint "eagle-import:CHIPLED_0603_NOOUTLINE")
      (libsource (lib "eagle-import") (part "LED0603_NOOUTLINE"))
    )
    (comp (ref "C7-20")
      (value "COLOR")
      (footprint "eagle-import:CHIPLED_0603_NOOUTLINE")
      (libsource (lib "eagle-import") (part "LED0603_NOOUTLINE"))
    )
    (comp (ref "C7-21")
      (value "COLOR")
      (footprint "eagle-import:CHIPLED_0603_NOOUTLINE")
      (libsource (lib "eagle-import") (part "LED0603_NOOUTLINE"))
    )
    (comp (ref "C7-22")
      (value "COLOR")
      (footprint "eagle-import:CHIPLED_0603_NOOUTLINE")
      (libsource (lib "eagle-import") (part "LED0603_NOOUTLINE"))
    )
    (comp (ref "C7-23")
      (value "COLOR")
      (footprint "eagle-import:CHIPLED_0603_NOOUTLINE")
      (libsource (lib "eagle-import") (part "LED0603_NOOUTLINE"))
    )
    (comp (ref "C7-24")
      (value "COLOR")
      (footprint "eagle-import:CHIPLED_0603_NOOUTLINE")
      (libsource (lib "eagle-import") (part "LED0603_NOOUTLINE"))
    )
    (comp (ref "C7-25")
      (value "COLOR")
      (footprint "eagle-import:CHIPLED_0603_NOOUTLINE")
      (libsource (lib "eagle-import") (part "LED0603_NOOUTLINE"))
    )
    (comp (ref "C7-26")
      (value "COLOR")
      (footprint "eagle-import:CHIPLED_0603_NOOUTLINE")
      (libsource (lib "eagle-import") (part "LED0603_NOOUTLINE"))
    )
    (comp (ref "C7-27")
      (value "COLOR")
      (footprint "eagle-import:CHIPLED_0603_NOOUTLINE")
      (libsource (lib "eagle-import") (part "LED0603_NOOUTLINE"))
    )
    (comp (ref "C7-28")
      (value "COLOR")
      (footprint "eagle-import:CHIPLED_0603_NOOUTLINE")
      (libsource (lib "eagle-import") (part "LED0603_NOOUTLINE"))
    )
    (comp (ref "C7-29")
      (value "COLOR")
      (footprint "eagle-import:CHIPLED_0603_NOOUTLINE")
      (libsource (lib "eagle-import") (part "LED0603_NOOUTLINE"))
    )
    (comp (ref "C7-30")
      (value "COLOR")
      (footprint "eagle-import:CHIPLED_0603_NOOUTLINE")
      (libsource (lib "eagle-import") (part "LED0603_NOOUTLINE"))
    )
    (comp (ref "C7-31")
      (value "COLOR")
      (footprint "eagle-import:CHIPLED_0603_NOOUTLINE")
      (libsource (lib "eagle-import") (part "LED0603_NOOUTLINE"))
    )
    (comp (ref "C7-32")
      (value "COLOR")
      (footprint "eagle-import:CHIPLED_0603_NOOUTLINE")
      (libsource (lib "eagle-import") (part "LED0603_NOOUTLINE"))
    )
    (comp (ref "C8-17")
      (value "COLOR")
      (footprint "eagle-import:CHIPLED_0603_NOOUTLINE")
      (libsource (lib "eagle-import") (part "LED0603_NOOUTLINE"))
    )
    (comp (ref "C8-18")
      (value "COLOR")
      (footprint "eagle-import:CHIPLED_0603_NOOUTLINE")
      (libsource (lib "eagle-import") (part "LED0603_NOOUTLINE"))
    )
    (comp (ref "C8-19")
      (value "COLOR")
      (footprint "eagle-import:CHIPLED_0603_NOOUTLINE")
      (libsource (lib "eagle-import") (part "LED0603_NOOUTLINE"))
    )
    (comp (ref "C8-20")
      (value "COLOR")
      (footprint "eagle-import:CHIPLED_0603_NOOUTLINE")
      (libsource (lib "eagle-import") (part "LED0603_NOOUTLINE"))
    )
    (comp (ref "C8-21")
      (value "COLOR")
      (footprint "eagle-import:CHIPLED_0603_NOOUTLINE")
      (libsource (lib "eagle-import") (part "LED0603_NOOUTLINE"))
    )
    (comp (ref "C8-22")
      (value "COLOR")
      (footprint "eagle-import:CHIPLED_0603_NOOUTLINE")
      (libsource (lib "eagle-import") (part "LED0603_NOOUTLINE"))
    )
    (comp (ref "C8-23")
      (value "COLOR")
      (footprint "eagle-import:CHIPLED_0603_NOOUTLINE")
      (libsource (lib "eagle-import") (part "LED0603_NOOUTLINE"))
    )
    (comp (ref "C8-24")
      (value "COLOR")
      (footprint "eagle-import:CHIPLED_0603_NOOUTLINE")
      (libsource (lib "eagle-import") (part "LED0603_NOOUTLINE"))
    )
    (comp (ref "C8-25")
      (value "COLOR")
      (footprint "eagle-import:CHIPLED_0603_NOOUTLINE")
      (libsource (lib "eagle-import") (part "LED0603_NOOUTLINE"))
    )
    (comp (ref "C8-26")
      (value "COLOR")
      (footprint "eagle-import:CHIPLED_0603_NOOUTLINE")
      (libsource (lib "eagle-import") (part "LED0603_NOOUTLINE"))
    )
    (comp (ref "C8-27")
      (value "COLOR")
      (footprint "eagle-import:CHIPLED_0603_NOOUTLINE")
      (libsource (lib "eagle-import") (part "LED0603_NOOUTLINE"))
    )
    (comp (ref "C8-28")
      (value "COLOR")
      (footprint "eagle-import:CHIPLED_0603_NOOUTLINE")
      (libsource (lib "eagle-import") (part "LED0603_NOOUTLINE"))
    )
    (comp (ref "C8-29")
      (value "COLOR")
      (footprint "eagle-import:CHIPLED_0603_NOOUTLINE")
      (libsource (lib "eagle-import") (part "LED0603_NOOUTLINE"))
    )
    (comp (ref "C8-30")
      (value "COLOR")
      (footprint "eagle-import:CHIPLED_0603_NOOUTLINE")
      (libsource (lib "eagle-import") (part "LED0603_NOOUTLINE"))
    )
    (comp (ref "C8-31")
      (value "COLOR")
      (footprint "eagle-import:CHIPLED_0603_NOOUTLINE")
      (libsource (lib "eagle-import") (part "LED0603_NOOUTLINE"))
    )
    (comp (ref "C8-32")
      (value "COLOR")
      (footprint "eagle-import:CHIPLED_0603_NOOUTLINE")
      (libsource (lib "eagle-import") (part "LED0603_NOOUTLINE"))
    )
    (comp (ref "C9-17")
      (value "COLOR")
      (footprint "eagle-import:CHIPLED_0603_NOOUTLINE")
      (libsource (lib "eagle-import") (part "LED0603_NOOUTLINE"))
    )
    (comp (ref "C9-18")
      (value "COLOR")
      (footprint "eagle-import:CHIPLED_0603_NOOUTLINE")
      (libsource (lib "eagle-import") (part "LED0603_NOOUTLINE"))
    )
    (comp (ref "C9-19")
      (value "COLOR")
      (footprint "eagle-import:CHIPLED_0603_NOOUTLINE")
      (libsource (lib "eagle-import") (part "LED0603_NOOUTLINE"))
    )
    (comp (ref "C9-20")
      (value "COLOR")
      (footprint "eagle-import:CHIPLED_0603_NOOUTLINE")
      (libsource (lib "eagle-import") (part "LED0603_NOOUTLINE"))
    )
    (comp (ref "C9-21")
      (value "COLOR")
      (footprint "eagle-import:CHIPLED_0603_NOOUTLINE")
      (libsource (lib "eagle-import") (part "LED0603_NOOUTLINE"))
    )
    (comp (ref "C9-22")
      (value "COLOR")
      (footprint "eagle-import:CHIPLED_0603_NOOUTLINE")
      (libsource (lib "eagle-import") (part "LED0603_NOOUTLINE"))
    )
    (comp (ref "C9-23")
      (value "COLOR")
      (footprint "eagle-import:CHIPLED_0603_NOOUTLINE")
      (libsource (lib "eagle-import") (part "LED0603_NOOUTLINE"))
    )
    (comp (ref "C9-24")
      (value "COLOR")
      (footprint "eagle-import:CHIPLED_0603_NOOUTLINE")
      (libsource (lib "eagle-import") (part "LED0603_NOOUTLINE"))
    )
    (comp (ref "C9-25")
      (value "COLOR")
      (footprint "eagle-import:CHIPLED_0603_NOOUTLINE")
      (libsource (lib "eagle-import") (part "LED0603_NOOUTLINE"))
    )
    (comp (ref "C9-26")
      (value "COLOR")
      (footprint "eagle-import:CHIPLED_0603_NOOUTLINE")
      (libsource (lib "eagle-import") (part "LED0603_NOOUTLINE"))
    )
    (comp (ref "C9-27")
      (value "COLOR")
      (footprint "eagle-import:CHIPLED_0603_NOOUTLINE")
      (libsource (lib "eagle-import") (part "LED0603_NOOUTLINE"))
    )
    (comp (ref "C9-28")
      (value "COLOR")
      (footprint "eagle-import:CHIPLED_0603_NOOUTLINE")
      (libsource (lib "eagle-import") (part "LED0603_NOOUTLINE"))
    )
    (comp (ref "C9-29")
      (value "COLOR")
      (footprint "eagle-import:CHIPLED_0603_NOOUTLINE")
      (libsource (lib "eagle-import") (part "LED0603_NOOUTLINE"))
    )
    (comp (ref "C9-30")
      (value "COLOR")
      (footprint "eagle-import:CHIPLED_0603_NOOUTLINE")
      (libsource (lib "eagle-import") (part "LED0603_NOOUTLINE"))
    )
    (comp (ref "C9-31")
      (value "COLOR")
      (footprint "eagle-import:CHIPLED_0603_NOOUTLINE")
      (libsource (lib "eagle-import") (part "LED0603_NOOUTLINE"))
    )
    (comp (ref "C9-32")
      (value "COLOR")
      (footprint "eagle-import:CHIPLED_0603_NOOUTLINE")
      (libsource (lib "eagle-import") (part "LED0603_NOOUTLINE"))
    )
    (comp (ref "C2")
      (value "0.1uF")
      (footprint "eagle-import:0603")
      (libsource (lib "eagle-import") (part "0.1UF-0603-25V-(+80/-20%)"))
    )
    (comp (ref "C5")
      (value "0.1uF")
      (footprint "eagle-import:0603")
      (libsource (lib "eagle-import") (part "0.1UF-0603-25V-(+80/-20%)"))
    )
    (comp (ref "C111")
      (value "10uF")
      (footprint "eagle-import:1206")
      (libsource (lib "eagle-import") (part "10UF-1206-6.3V-20%"))
    )
    (comp (ref "JP2")
      (value "FIDUCIAL1X2")
      (footprint "eagle-import:FIDUCIAL-1X2")
      (libsource (lib "eagle-import") (part "FIDUCIAL1X2"))
    )
    (comp (ref "JP3")
      (value "FIDUCIAL1X2")
      (footprint "eagle-import:FIDUCIAL-1X2")
      (libsource (lib "eagle-import") (part "FIDUCIAL1X2"))
    )
    (comp (ref "JP4")
      (value "FIDUCIAL1X2")
      (footprint "eagle-import:FIDUCIAL-1X2")
      (libsource (lib "eagle-import") (part "FIDUCIAL1X2"))
    )
    (comp (ref "R1")
      (value "20k")
      (footprint "eagle-import:0603")
      (libsource (lib "eagle-import") (part "20KOHM-0603-1/10W-1%"))
    )
    (comp (ref "R2")
      (value "20k")
      (footprint "eagle-import:0603")
      (libsource (lib "eagle-import") (part "20KOHM-0603-1/10W-1%"))
    )
    (comp (ref "R3")
      (value "20k")
      (footprint "eagle-import:0603")
      (libsource (lib "eagle-import") (part "20KOHM-0603-1/10W-1%"))
    )
    (comp (ref "R4")
      (value "4.7k")
      (footprint "eagle-import:0603")
      (libsource (lib "eagle-import") (part "4.7KOHM-0603-1/10W-1%"))
    )
    (comp (ref "R5")
      (value "4.7k")
      (footprint "eagle-import:0603")
      (libsource (lib "eagle-import") (part "4.7KOHM-0603-1/10W-1%"))
    )
    (comp (ref "R14")
      (value "20k")
      (footprint "eagle-import:0603")
      (libsource (lib "eagle-import") (part "20KOHM-0603-1/10W-1%"))
    )
    (comp (ref "U4")
      (value "IS31FL3731")
      (footprint "eagle-import:QFN28")
      (libsource (lib "eagle-import") (part "IS31FL3731"))
    )
    (comp (ref "C1-1")
      (value "COLOR")
      (footprint "eagle-import:CHIPLED_0603_NOOUTLINE")
      (libsource (lib "eagle-import") (part "LED0603_NOOUTLINE"))
    )
    (comp (ref "C1-2")
      (value "COLOR")
      (footprint "eagle-import:CHIPLED_0603_NOOUTLINE")
      (libsource (lib "eagle-import") (part "LED0603_NOOUTLINE"))
    )
    (comp (ref "C1-3")
      (value "COLOR")
      (footprint "eagle-import:CHIPLED_0603_NOOUTLINE")
      (libsource (lib "eagle-import") (part "LED0603_NOOUTLINE"))
    )
    (comp (ref "C1-4")
      (value "COLOR")
      (footprint "eagle-import:CHIPLED_0603_NOOUTLINE")
      (libsource (lib "eagle-import") (part "LED0603_NOOUTLINE"))
    )
    (comp (ref "C1-5")
      (value "COLOR")
      (footprint "eagle-import:CHIPLED_0603_NOOUTLINE")
      (libsource (lib "eagle-import") (part "LED0603_NOOUTLINE"))
    )
    (comp (ref "C1-6")
      (value "COLOR")
      (footprint "eagle-import:CHIPLED_0603_NOOUTLINE")
      (libsource (lib "eagle-import") (part "LED0603_NOOUTLINE"))
    )
    (comp (ref "C1-7")
      (value "COLOR")
      (footprint "eagle-import:CHIPLED_0603_NOOUTLINE")
      (libsource (lib "eagle-import") (part "LED0603_NOOUTLINE"))
    )
    (comp (ref "C1-8")
      (value "COLOR")
      (footprint "eagle-import:CHIPLED_0603_NOOUTLINE")
      (libsource (lib "eagle-import") (part "LED0603_NOOUTLINE"))
    )
    (comp (ref "C1-9")
      (value "COLOR")
      (footprint "eagle-import:CHIPLED_0603_NOOUTLINE")
      (libsource (lib "eagle-import") (part "LED0603_NOOUTLINE"))
    )
    (comp (ref "C1-10")
      (value "COLOR")
      (footprint "eagle-import:CHIPLED_0603_NOOUTLINE")
      (libsource (lib "eagle-import") (part "LED0603_NOOUTLINE"))
    )
    (comp (ref "C1-11")
      (value "COLOR")
      (footprint "eagle-import:CHIPLED_0603_NOOUTLINE")
      (libsource (lib "eagle-import") (part "LED0603_NOOUTLINE"))
    )
    (comp (ref "C1-12")
      (value "COLOR")
      (footprint "eagle-import:CHIPLED_0603_NOOUTLINE")
      (libsource (lib "eagle-import") (part "LED0603_NOOUTLINE"))
    )
    (comp (ref "C1-13")
      (value "COLOR")
      (footprint "eagle-import:CHIPLED_0603_NOOUTLINE")
      (libsource (lib "eagle-import") (part "LED0603_NOOUTLINE"))
    )
    (comp (ref "C1-14")
      (value "COLOR")
      (footprint "eagle-import:CHIPLED_0603_NOOUTLINE")
      (libsource (lib "eagle-import") (part "LED0603_NOOUTLINE"))
    )
    (comp (ref "C1-15")
      (value "COLOR")
      (footprint "eagle-import:CHIPLED_0603_NOOUTLINE")
      (libsource (lib "eagle-import") (part "LED0603_NOOUTLINE"))
    )
    (comp (ref "C1-16")
      (value "COLOR")
      (footprint "eagle-import:CHIPLED_0603_NOOUTLINE")
      (libsource (lib "eagle-import") (part "LED0603_NOOUTLINE"))
    )
    (comp (ref "C2-1")
      (value "COLOR")
      (footprint "eagle-import:CHIPLED_0603_NOOUTLINE")
      (libsource (lib "eagle-import") (part "LED0603_NOOUTLINE"))
    )
    (comp (ref "C2-2")
      (value "COLOR")
      (footprint "eagle-import:CHIPLED_0603_NOOUTLINE")
      (libsource (lib "eagle-import") (part "LED0603_NOOUTLINE"))
    )
    (comp (ref "C2-3")
      (value "COLOR")
      (footprint "eagle-import:CHIPLED_0603_NOOUTLINE")
      (libsource (lib "eagle-import") (part "LED0603_NOOUTLINE"))
    )
    (comp (ref "C2-4")
      (value "COLOR")
      (footprint "eagle-import:CHIPLED_0603_NOOUTLINE")
      (libsource (lib "eagle-import") (part "LED0603_NOOUTLINE"))
    )
    (comp (ref "C2-5")
      (value "COLOR")
      (footprint "eagle-import:CHIPLED_0603_NOOUTLINE")
      (libsource (lib "eagle-import") (part "LED0603_NOOUTLINE"))
    )
    (comp (ref "C2-6")
      (value "COLOR")
      (footprint "eagle-import:CHIPLED_0603_NOOUTLINE")
      (libsource (lib "eagle-import") (part "LED0603_NOOUTLINE"))
    )
    (comp (ref "C2-7")
      (value "COLOR")
      (footprint "eagle-import:CHIPLED_0603_NOOUTLINE")
      (libsource (lib "eagle-import") (part "LED0603_NOOUTLINE"))
    )
    (comp (ref "C2-8")
      (value "COLOR")
      (footprint "eagle-import:CHIPLED_0603_NOOUTLINE")
      (libsource (lib "eagle-import") (part "LED0603_NOOUTLINE"))
    )
    (comp (ref "C2-9")
      (value "COLOR")
      (footprint "eagle-import:CHIPLED_0603_NOOUTLINE")
      (libsource (lib "eagle-import") (part "LED0603_NOOUTLINE"))
    )
    (comp (ref "C2-10")
      (value "COLOR")
      (footprint "eagle-import:CHIPLED_0603_NOOUTLINE")
      (libsource (lib "eagle-import") (part "LED0603_NOOUTLINE"))
    )
    (comp (ref "C2-11")
      (value "COLOR")
      (footprint "eagle-import:CHIPLED_0603_NOOUTLINE")
      (libsource (lib "eagle-import") (part "LED0603_NOOUTLINE"))
    )
    (comp (ref "C2-12")
      (value "COLOR")
      (footprint "eagle-import:CHIPLED_0603_NOOUTLINE")
      (libsource (lib "eagle-import") (part "LED0603_NOOUTLINE"))
    )
    (comp (ref "C2-13")
      (value "COLOR")
      (footprint "eagle-import:CHIPLED_0603_NOOUTLINE")
      (libsource (lib "eagle-import") (part "LED0603_NOOUTLINE"))
    )
    (comp (ref "C2-14")
      (value "COLOR")
      (footprint "eagle-import:CHIPLED_0603_NOOUTLINE")
      (libsource (lib "eagle-import") (part "LED0603_NOOUTLINE"))
    )
    (comp (ref "C2-15")
      (value "COLOR")
      (footprint "eagle-import:CHIPLED_0603_NOOUTLINE")
      (libsource (lib "eagle-import") (part "LED0603_NOOUTLINE"))
    )
    (comp (ref "C2-16")
      (value "COLOR")
      (footprint "eagle-import:CHIPLED_0603_NOOUTLINE")
      (libsource (lib "eagle-import") (part "LED0603_NOOUTLINE"))
    )
    (comp (ref "C3-1")
      (value "COLOR")
      (footprint "eagle-import:CHIPLED_0603_NOOUTLINE")
      (libsource (lib "eagle-import") (part "LED0603_NOOUTLINE"))
    )
    (comp (ref "C3-2")
      (value "COLOR")
      (footprint "eagle-import:CHIPLED_0603_NOOUTLINE")
      (libsource (lib "eagle-import") (part "LED0603_NOOUTLINE"))
    )
    (comp (ref "C3-3")
      (value "COLOR")
      (footprint "eagle-import:CHIPLED_0603_NOOUTLINE")
      (libsource (lib "eagle-import") (part "LED0603_NOOUTLINE"))
    )
    (comp (ref "C3-4")
      (value "COLOR")
      (footprint "eagle-import:CHIPLED_0603_NOOUTLINE")
      (libsource (lib "eagle-import") (part "LED0603_NOOUTLINE"))
    )
    (comp (ref "C3-5")
      (value "COLOR")
      (footprint "eagle-import:CHIPLED_0603_NOOUTLINE")
      (libsource (lib "eagle-import") (part "LED0603_NOOUTLINE"))
    )
    (comp (ref "C3-6")
      (value "COLOR")
      (footprint "eagle-import:CHIPLED_0603_NOOUTLINE")
      (libsource (lib "eagle-import") (part "LED0603_NOOUTLINE"))
    )
    (comp (ref "C3-7")
      (value "COLOR")
      (footprint "eagle-import:CHIPLED_0603_NOOUTLINE")
      (libsource (lib "eagle-import") (part "LED0603_NOOUTLINE"))
    )
    (comp (ref "C3-8")
      (value "COLOR")
      (footprint "eagle-import:CHIPLED_0603_NOOUTLINE")
      (libsource (lib "eagle-import") (part "LED0603_NOOUTLINE"))
    )
    (comp (ref "C3-9")
      (value "COLOR")
      (footprint "eagle-import:CHIPLED_0603_NOOUTLINE")
      (libsource (lib "eagle-import") (part "LED0603_NOOUTLINE"))
    )
    (comp (ref "C3-10")
      (value "COLOR")
      (footprint "eagle-import:CHIPLED_0603_NOOUTLINE")
      (libsource (lib "eagle-import") (part "LED0603_NOOUTLINE"))
    )
    (comp (ref "C3-11")
      (value "COLOR")
      (footprint "eagle-import:CHIPLED_0603_NOOUTLINE")
      (libsource (lib "eagle-import") (part "LED0603_NOOUTLINE"))
    )
    (comp (ref "C3-12")
      (value "COLOR")
      (footprint "eagle-import:CHIPLED_0603_NOOUTLINE")
      (libsource (lib "eagle-import") (part "LED0603_NOOUTLINE"))
    )
    (comp (ref "C3-13")
      (value "COLOR")
      (footprint "eagle-import:CHIPLED_0603_NOOUTLINE")
      (libsource (lib "eagle-import") (part "LED0603_NOOUTLINE"))
    )
    (comp (ref "C3-14")
      (value "COLOR")
      (footprint "eagle-import:CHIPLED_0603_NOOUTLINE")
      (libsource (lib "eagle-import") (part "LED0603_NOOUTLINE"))
    )
    (comp (ref "C3-15")
      (value "COLOR")
      (footprint "eagle-import:CHIPLED_0603_NOOUTLINE")
      (libsource (lib "eagle-import") (part "LED0603_NOOUTLINE"))
    )
    (comp (ref "C3-16")
      (value "COLOR")
      (footprint "eagle-import:CHIPLED_0603_NOOUTLINE")
      (libsource (lib "eagle-import") (part "LED0603_NOOUTLINE"))
    )
    (comp (ref "C4-1")
      (value "COLOR")
      (footprint "eagle-import:CHIPLED_0603_NOOUTLINE")
      (libsource (lib "eagle-import") (part "LED0603_NOOUTLINE"))
    )
    (comp (ref "C4-2")
      (value "COLOR")
      (footprint "eagle-import:CHIPLED_0603_NOOUTLINE")
      (libsource (lib "eagle-import") (part "LED0603_NOOUTLINE"))
    )
    (comp (ref "C4-3")
      (value "COLOR")
      (footprint "eagle-import:CHIPLED_0603_NOOUTLINE")
      (libsource (lib "eagle-import") (part "LED0603_NOOUTLINE"))
    )
    (comp (ref "C4-4")
      (value "COLOR")
      (footprint "eagle-import:CHIPLED_0603_NOOUTLINE")
      (libsource (lib "eagle-import") (part "LED0603_NOOUTLINE"))
    )
    (comp (ref "C4-5")
      (value "COLOR")
      (footprint "eagle-import:CHIPLED_0603_NOOUTLINE")
      (libsource (lib "eagle-import") (part "LED0603_NOOUTLINE"))
    )
    (comp (ref "C4-6")
      (value "COLOR")
      (footprint "eagle-import:CHIPLED_0603_NOOUTLINE")
      (libsource (lib "eagle-import") (part "LED0603_NOOUTLINE"))
    )
    (comp (ref "C4-7")
      (value "COLOR")
      (footprint "eagle-import:CHIPLED_0603_NOOUTLINE")
      (libsource (lib "eagle-import") (part "LED0603_NOOUTLINE"))
    )
    (comp (ref "C4-8")
      (value "COLOR")
      (footprint "eagle-import:CHIPLED_0603_NOOUTLINE")
      (libsource (lib "eagle-import") (part "LED0603_NOOUTLINE"))
    )
    (comp (ref "C4-9")
      (value "COLOR")
      (footprint "eagle-import:CHIPLED_0603_NOOUTLINE")
      (libsource (lib "eagle-import") (part "LED0603_NOOUTLINE"))
    )
    (comp (ref "C4-10")
      (value "COLOR")
      (footprint "eagle-import:CHIPLED_0603_NOOUTLINE")
      (libsource (lib "eagle-import") (part "LED0603_NOOUTLINE"))
    )
    (comp (ref "C4-11")
      (value "COLOR")
      (footprint "eagle-import:CHIPLED_0603_NOOUTLINE")
      (libsource (lib "eagle-import") (part "LED0603_NOOUTLINE"))
    )
    (comp (ref "C4-12")
      (value "COLOR")
      (footprint "eagle-import:CHIPLED_0603_NOOUTLINE")
      (libsource (lib "eagle-import") (part "LED0603_NOOUTLINE"))
    )
    (comp (ref "C4-13")
      (value "COLOR")
      (footprint "eagle-import:CHIPLED_0603_NOOUTLINE")
      (libsource (lib "eagle-import") (part "LED0603_NOOUTLINE"))
    )
    (comp (ref "C4-14")
      (value "COLOR")
      (footprint "eagle-import:CHIPLED_0603_NOOUTLINE")
      (libsource (lib "eagle-import") (part "LED0603_NOOUTLINE"))
    )
    (comp (ref "C4-15")
      (value "COLOR")
      (footprint "eagle-import:CHIPLED_0603_NOOUTLINE")
      (libsource (lib "eagle-import") (part "LED0603_NOOUTLINE"))
    )
    (comp (ref "C4-16")
      (value "COLOR")
      (footprint "eagle-import:CHIPLED_0603_NOOUTLINE")
      (libsource (lib "eagle-import") (part "LED0603_NOOUTLINE"))
    )
    (comp (ref "C5-1")
      (value "COLOR")
      (footprint "eagle-import:CHIPLED_0603_NOOUTLINE")
      (libsource (lib "eagle-import") (part "LED0603_NOOUTLINE"))
    )
    (comp (ref "C5-2")
      (value "COLOR")
      (footprint "eagle-import:CHIPLED_0603_NOOUTLINE")
      (libsource (lib "eagle-import") (part "LED0603_NOOUTLINE"))
    )
    (comp (ref "C5-3")
      (value "COLOR")
      (footprint "eagle-import:CHIPLED_0603_NOOUTLINE")
      (libsource (lib "eagle-import") (part "LED0603_NOOUTLINE"))
    )
    (comp (ref "C5-4")
      (value "COLOR")
      (footprint "eagle-import:CHIPLED_0603_NOOUTLINE")
      (libsource (lib "eagle-import") (part "LED0603_NOOUTLINE"))
    )
    (comp (ref "C5-5")
      (value "COLOR")
      (footprint "eagle-import:CHIPLED_0603_NOOUTLINE")
      (libsource (lib "eagle-import") (part "LED0603_NOOUTLINE"))
    )
    (comp (ref "C5-6")
      (value "COLOR")
      (footprint "eagle-import:CHIPLED_0603_NOOUTLINE")
      (libsource (lib "eagle-import") (part "LED0603_NOOUTLINE"))
    )
    (comp (ref "C5-7")
      (value "COLOR")
      (footprint "eagle-import:CHIPLED_0603_NOOUTLINE")
      (libsource (lib "eagle-import") (part "LED0603_NOOUTLINE"))
    )
    (comp (ref "C5-8")
      (value "COLOR")
      (footprint "eagle-import:CHIPLED_0603_NOOUTLINE")
      (libsource (lib "eagle-import") (part "LED0603_NOOUTLINE"))
    )
    (comp (ref "C5-9")
      (value "COLOR")
      (footprint "eagle-import:CHIPLED_0603_NOOUTLINE")
      (libsource (lib "eagle-import") (part "LED0603_NOOUTLINE"))
    )
    (comp (ref "C5-10")
      (value "COLOR")
      (footprint "eagle-import:CHIPLED_0603_NOOUTLINE")
      (libsource (lib "eagle-import") (part "LED0603_NOOUTLINE"))
    )
    (comp (ref "C5-11")
      (value "COLOR")
      (footprint "eagle-import:CHIPLED_0603_NOOUTLINE")
      (libsource (lib "eagle-import") (part "LED0603_NOOUTLINE"))
    )
    (comp (ref "C5-12")
      (value "COLOR")
      (footprint "eagle-import:CHIPLED_0603_NOOUTLINE")
      (libsource (lib "eagle-import") (part "LED0603_NOOUTLINE"))
    )
    (comp (ref "C5-13")
      (value "COLOR")
      (footprint "eagle-import:CHIPLED_0603_NOOUTLINE")
      (libsource (lib "eagle-import") (part "LED0603_NOOUTLINE"))
    )
    (comp (ref "C5-14")
      (value "COLOR")
      (footprint "eagle-import:CHIPLED_0603_NOOUTLINE")
      (libsource (lib "eagle-import") (part "LED0603_NOOUTLINE"))
    )
    (comp (ref "C5-15")
      (value "COLOR")
      (footprint "eagle-import:CHIPLED_0603_NOOUTLINE")
      (libsource (lib "eagle-import") (part "LED0603_NOOUTLINE"))
    )
    (comp (ref "C5-16")
      (value "COLOR")
      (footprint "eagle-import:CHIPLED_0603_NOOUTLINE")
      (libsource (lib "eagle-import") (part "LED0603_NOOUTLINE"))
    )
    (comp (ref "C6-1")
      (value "COLOR")
      (footprint "eagle-import:CHIPLED_0603_NOOUTLINE")
      (libsource (lib "eagle-import") (part "LED0603_NOOUTLINE"))
    )
    (comp (ref "C6-2")
      (value "COLOR")
      (footprint "eagle-import:CHIPLED_0603_NOOUTLINE")
      (libsource (lib "eagle-import") (part "LED0603_NOOUTLINE"))
    )
    (comp (ref "C6-3")
      (value "COLOR")
      (footprint "eagle-import:CHIPLED_0603_NOOUTLINE")
      (libsource (lib "eagle-import") (part "LED0603_NOOUTLINE"))
    )
    (comp (ref "C6-4")
      (value "COLOR")
      (footprint "eagle-import:CHIPLED_0603_NOOUTLINE")
      (libsource (lib "eagle-import") (part "LED0603_NOOUTLINE"))
    )
    (comp (ref "C6-5")
      (value "COLOR")
      (footprint "eagle-import:CHIPLED_0603_NOOUTLINE")
      (libsource (lib "eagle-import") (part "LED0603_NOOUTLINE"))
    )
    (comp (ref "C6-6")
      (value "COLOR")
      (footprint "eagle-import:CHIPLED_0603_NOOUTLINE")
      (libsource (lib "eagle-import") (part "LED0603_NOOUTLINE"))
    )
    (comp (ref "C6-7")
      (value "COLOR")
      (footprint "eagle-import:CHIPLED_0603_NOOUTLINE")
      (libsource (lib "eagle-import") (part "LED0603_NOOUTLINE"))
    )
    (comp (ref "C6-8")
      (value "COLOR")
      (footprint "eagle-import:CHIPLED_0603_NOOUTLINE")
      (libsource (lib "eagle-import") (part "LED0603_NOOUTLINE"))
    )
    (comp (ref "C6-9")
      (value "COLOR")
      (footprint "eagle-import:CHIPLED_0603_NOOUTLINE")
      (libsource (lib "eagle-import") (part "LED0603_NOOUTLINE"))
    )
    (comp (ref "C6-10")
      (value "COLOR")
      (footprint "eagle-import:CHIPLED_0603_NOOUTLINE")
      (libsource (lib "eagle-import") (part "LED0603_NOOUTLINE"))
    )
    (comp (ref "C6-11")
      (value "COLOR")
      (footprint "eagle-import:CHIPLED_0603_NOOUTLINE")
      (libsource (lib "eagle-import") (part "LED0603_NOOUTLINE"))
    )
    (comp (ref "C6-12")
      (value "COLOR")
      (footprint "eagle-import:CHIPLED_0603_NOOUTLINE")
      (libsource (lib "eagle-import") (part "LED0603_NOOUTLINE"))
    )
    (comp (ref "C6-13")
      (value "COLOR")
      (footprint "eagle-import:CHIPLED_0603_NOOUTLINE")
      (libsource (lib "eagle-import") (part "LED0603_NOOUTLINE"))
    )
    (comp (ref "C6-14")
      (value "COLOR")
      (footprint "eagle-import:CHIPLED_0603_NOOUTLINE")
      (libsource (lib "eagle-import") (part "LED0603_NOOUTLINE"))
    )
    (comp (ref "C6-15")
      (value "COLOR")
      (footprint "eagle-import:CHIPLED_0603_NOOUTLINE")
      (libsource (lib "eagle-import") (part "LED0603_NOOUTLINE"))
    )
    (comp (ref "C6-16")
      (value "COLOR")
      (footprint "eagle-import:CHIPLED_0603_NOOUTLINE")
      (libsource (lib "eagle-import") (part "LED0603_NOOUTLINE"))
    )
    (comp (ref "C7-1")
      (value "COLOR")
      (footprint "eagle-import:CHIPLED_0603_NOOUTLINE")
      (libsource (lib "eagle-import") (part "LED0603_NOOUTLINE"))
    )
    (comp (ref "C7-2")
      (value "COLOR")
      (footprint "eagle-import:CHIPLED_0603_NOOUTLINE")
      (libsource (lib "eagle-import") (part "LED0603_NOOUTLINE"))
    )
    (comp (ref "C7-3")
      (value "COLOR")
      (footprint "eagle-import:CHIPLED_0603_NOOUTLINE")
      (libsource (lib "eagle-import") (part "LED0603_NOOUTLINE"))
    )
    (comp (ref "C7-4")
      (value "COLOR")
      (footprint "eagle-import:CHIPLED_0603_NOOUTLINE")
      (libsource (lib "eagle-import") (part "LED0603_NOOUTLINE"))
    )
    (comp (ref "C7-5")
      (value "COLOR")
      (footprint "eagle-import:CHIPLED_0603_NOOUTLINE")
      (libsource (lib "eagle-import") (part "LED0603_NOOUTLINE"))
    )
    (comp (ref "C7-6")
      (value "COLOR")
      (footprint "eagle-import:CHIPLED_0603_NOOUTLINE")
      (libsource (lib "eagle-import") (part "LED0603_NOOUTLINE"))
    )
    (comp (ref "C7-7")
      (value "COLOR")
      (footprint "eagle-import:CHIPLED_0603_NOOUTLINE")
      (libsource (lib "eagle-import") (part "LED0603_NOOUTLINE"))
    )
    (comp (ref "C7-8")
      (value "COLOR")
      (footprint "eagle-import:CHIPLED_0603_NOOUTLINE")
      (libsource (lib "eagle-import") (part "LED0603_NOOUTLINE"))
    )
    (comp (ref "C7-9")
      (value "COLOR")
      (footprint "eagle-import:CHIPLED_0603_NOOUTLINE")
      (libsource (lib "eagle-import") (part "LED0603_NOOUTLINE"))
    )
    (comp (ref "C7-10")
      (value "COLOR")
      (footprint "eagle-import:CHIPLED_0603_NOOUTLINE")
      (libsource (lib "eagle-import") (part "LED0603_NOOUTLINE"))
    )
    (comp (ref "C7-11")
      (value "COLOR")
      (footprint "eagle-import:CHIPLED_0603_NOOUTLINE")
      (libsource (lib "eagle-import") (part "LED0603_NOOUTLINE"))
    )
    (comp (ref "C7-12")
      (value "COLOR")
      (footprint "eagle-import:CHIPLED_0603_NOOUTLINE")
      (libsource (lib "eagle-import") (part "LED0603_NOOUTLINE"))
    )
    (comp (ref "C7-13")
      (value "COLOR")
      (footprint "eagle-import:CHIPLED_0603_NOOUTLINE")
      (libsource (lib "eagle-import") (part "LED0603_NOOUTLINE"))
    )
    (comp (ref "C7-14")
      (value "COLOR")
      (footprint "eagle-import:CHIPLED_0603_NOOUTLINE")
      (libsource (lib "eagle-import") (part "LED0603_NOOUTLINE"))
    )
    (comp (ref "C7-15")
      (value "COLOR")
      (footprint "eagle-import:CHIPLED_0603_NOOUTLINE")
      (libsource (lib "eagle-import") (part "LED0603_NOOUTLINE"))
    )
    (comp (ref "C7-16")
      (value "COLOR")
      (footprint "eagle-import:CHIPLED_0603_NOOUTLINE")
      (libsource (lib "eagle-import") (part "LED0603_NOOUTLINE"))
    )
    (comp (ref "C8-1")
      (value "COLOR")
      (footprint "eagle-import:CHIPLED_0603_NOOUTLINE")
      (libsource (lib "eagle-import") (part "LED0603_NOOUTLINE"))
    )
    (comp (ref "C8-2")
      (value "COLOR")
      (footprint "eagle-import:CHIPLED_0603_NOOUTLINE")
      (libsource (lib "eagle-import") (part "LED0603_NOOUTLINE"))
    )
    (comp (ref "C8-3")
      (value "COLOR")
      (footprint "eagle-import:CHIPLED_0603_NOOUTLINE")
      (libsource (lib "eagle-import") (part "LED0603_NOOUTLINE"))
    )
    (comp (ref "C8-4")
      (value "COLOR")
      (footprint "eagle-import:CHIPLED_0603_NOOUTLINE")
      (libsource (lib "eagle-import") (part "LED0603_NOOUTLINE"))
    )
    (comp (ref "C8-5")
      (value "COLOR")
      (footprint "eagle-import:CHIPLED_0603_NOOUTLINE")
      (libsource (lib "eagle-import") (part "LED0603_NOOUTLINE"))
    )
    (comp (ref "C8-6")
      (value "COLOR")
      (footprint "eagle-import:CHIPLED_0603_NOOUTLINE")
      (libsource (lib "eagle-import") (part "LED0603_NOOUTLINE"))
    )
    (comp (ref "C8-7")
      (value "COLOR")
      (footprint "eagle-import:CHIPLED_0603_NOOUTLINE")
      (libsource (lib "eagle-import") (part "LED0603_NOOUTLINE"))
    )
    (comp (ref "C8-8")
      (value "COLOR")
      (footprint "eagle-import:CHIPLED_0603_NOOUTLINE")
      (libsource (lib "eagle-import") (part "LED0603_NOOUTLINE"))
    )
    (comp (ref "C8-9")
      (value "COLOR")
      (footprint "eagle-import:CHIPLED_0603_NOOUTLINE")
      (libsource (lib "eagle-import") (part "LED0603_NOOUTLINE"))
    )
    (comp (ref "C8-10")
      (value "COLOR")
      (footprint "eagle-import:CHIPLED_0603_NOOUTLINE")
      (libsource (lib "eagle-import") (part "LED0603_NOOUTLINE"))
    )
    (comp (ref "C8-11")
      (value "COLOR")
      (footprint "eagle-import:CHIPLED_0603_NOOUTLINE")
      (libsource (lib "eagle-import") (part "LED0603_NOOUTLINE"))
    )
    (comp (ref "C8-12")
      (value "COLOR")
      (footprint "eagle-import:CHIPLED_0603_NOOUTLINE")
      (libsource (lib "eagle-import") (part "LED0603_NOOUTLINE"))
    )
    (comp (ref "C8-13")
      (value "COLOR")
      (footprint "eagle-import:CHIPLED_0603_NOOUTLINE")
      (libsource (lib "eagle-import") (part "LED0603_NOOUTLINE"))
    )
    (comp (ref "C8-14")
      (value "COLOR")
      (footprint "eagle-import:CHIPLED_0603_NOOUTLINE")
      (libsource (lib "eagle-import") (part "LED0603_NOOUTLINE"))
    )
    (comp (ref "C8-15")
      (value "COLOR")
      (footprint "eagle-import:CHIPLED_0603_NOOUTLINE")
      (libsource (lib "eagle-import") (part "LED0603_NOOUTLINE"))
    )
    (comp (ref "C8-16")
      (value "COLOR")
      (footprint "eagle-import:CHIPLED_0603_NOOUTLINE")
      (libsource (lib "eagle-import") (part "LED0603_NOOUTLINE"))
    )
    (comp (ref "C9-1")
      (value "COLOR")
      (footprint "eagle-import:CHIPLED_0603_NOOUTLINE")
      (libsource (lib "eagle-import") (part "LED0603_NOOUTLINE"))
    )
    (comp (ref "C9-2")
      (value "COLOR")
      (footprint "eagle-import:CHIPLED_0603_NOOUTLINE")
      (libsource (lib "eagle-import") (part "LED0603_NOOUTLINE"))
    )
    (comp (ref "C9-3")
      (value "COLOR")
      (footprint "eagle-import:CHIPLED_0603_NOOUTLINE")
      (libsource (lib "eagle-import") (part "LED0603_NOOUTLINE"))
    )
    (comp (ref "C9-4")
      (value "COLOR")
      (footprint "eagle-import:CHIPLED_0603_NOOUTLINE")
      (libsource (lib "eagle-import") (part "LED0603_NOOUTLINE"))
    )
    (comp (ref "C9-5")
      (value "COLOR")
      (footprint "eagle-import:CHIPLED_0603_NOOUTLINE")
      (libsource (lib "eagle-import") (part "LED0603_NOOUTLINE"))
    )
    (comp (ref "C9-6")
      (value "COLOR")
      (footprint "eagle-import:CHIPLED_0603_NOOUTLINE")
      (libsource (lib "eagle-import") (part "LED0603_NOOUTLINE"))
    )
    (comp (ref "C9-7")
      (value "COLOR")
      (footprint "eagle-import:CHIPLED_0603_NOOUTLINE")
      (libsource (lib "eagle-import") (part "LED0603_NOOUTLINE"))
    )
    (comp (ref "C9-8")
      (value "COLOR")
      (footprint "eagle-import:CHIPLED_0603_NOOUTLINE")
      (libsource (lib "eagle-import") (part "LED0603_NOOUTLINE"))
    )
    (comp (ref "C9-9")
      (value "COLOR")
      (footprint "eagle-import:CHIPLED_0603_NOOUTLINE")
      (libsource (lib "eagle-import") (part "LED0603_NOOUTLINE"))
    )
    (comp (ref "C9-10")
      (value "COLOR")
      (footprint "eagle-import:CHIPLED_0603_NOOUTLINE")
      (libsource (lib "eagle-import") (part "LED0603_NOOUTLINE"))
    )
    (comp (ref "C9-11")
      (value "COLOR")
      (footprint "eagle-import:CHIPLED_0603_NOOUTLINE")
      (libsource (lib "eagle-import") (part "LED0603_NOOUTLINE"))
    )
    (comp (ref "C9-12")
      (value "COLOR")
      (footprint "eagle-import:CHIPLED_0603_NOOUTLINE")
      (libsource (lib "eagle-import") (part "LED0603_NOOUTLINE"))
    )
    (comp (ref "C9-13")
      (value "COLOR")
      (footprint "eagle-import:CHIPLED_0603_NOOUTLINE")
      (libsource (lib "eagle-import") (part "LED0603_NOOUTLINE"))
    )
    (comp (ref "C9-14")
      (value "COLOR")
      (footprint "eagle-import:CHIPLED_0603_NOOUTLINE")
      (libsource (lib "eagle-import") (part "LED0603_NOOUTLINE"))
    )
    (comp (ref "C9-15")
      (value "COLOR")
      (footprint "eagle-import:CHIPLED_0603_NOOUTLINE")
      (libsource (lib "eagle-import") (part "LED0603_NOOUTLINE"))
    )
    (comp (ref "C9-16")
      (value "COLOR")
      (footprint "eagle-import:CHIPLED_0603_NOOUTLINE")
      (libsource (lib "eagle-import") (part "LED0603_NOOUTLINE"))
    )
    (comp (ref "C6")
      (value "10uF")
      (footprint "eagle-import:1206")
      (libsource (lib "eagle-import") (part "10UF-1206-6.3V-20%"))
    )
    (comp (ref "C10")
      (value "0.1uF")
      (footprint "eagle-import:0603")
      (libsource (lib "eagle-import") (part "0.1UF-0603-25V-(+80/-20%)"))
    )
    (comp (ref "C12")
      (value "0.1uF")
      (footprint "eagle-import:0603")
      (libsource (lib "eagle-import") (part "0.1UF-0603-25V-(+80/-20%)"))
    )
    (comp (ref "R6")
      (value "20k")
      (footprint "eagle-import:0603")
      (libsource (lib "eagle-import") (part "20KOHM-0603-1/10W-1%"))
    )
    (comp (ref "R7")
      (value "20k")
      (footprint "eagle-import:0603")
      (libsource (lib "eagle-import") (part "20KOHM-0603-1/10W-1%"))
    )
    (comp (ref "R8")
      (value "20k")
      (footprint "eagle-import:0603")
      (libsource (lib "eagle-import") (part "20KOHM-0603-1/10W-1%"))
    )
    (comp (ref "U2")
      (value "IS31FL3731")
      (footprint "eagle-import:QFN28")
      (libsource (lib "eagle-import") (part "IS31FL3731"))
    )
  )
  (nets
    (net (code "1") (name "3.3V") (class "Default")
      (node (ref "C3") (pin "1") (pinfunction "1_1") (pintype "passive"))
      (node (ref "C4") (pin "1") (pinfunction "1_1") (pintype "passive"))
      (node (ref "J3") (pin "2") (pinfunction "2_2") (pintype "power_in"))
      (node (ref "R10") (pin "2") (pinfunction "2_2") (pintype "passive"))
      (node (ref "R18") (pin "2") (pinfunction "2_2") (pintype "passive"))
      (node (ref "R19") (pin "2") (pinfunction "2_2") (pintype "passive"))
      (node (ref "R20") (pin "2") (pinfunction "2_2") (pintype "passive"))
      (node (ref "U$12") (pin "1") (pinfunction "PAD_1") (pintype "bidirectional"))
      (node (ref "U$3") (pin "2") (pinfunction "VCC_2") (pintype "bidirectional"))
      (node (ref "U$9") (pin "5") (pinfunction "VOUT_5") (pintype "bidirectional"))
      (node (ref "X1") (pin "8") (pinfunction "VCC_8") (pintype "power_in"))
    )
    (net (code "2") (name "ADC") (class "Default")
      (node (ref "R12") (pin "1") (pinfunction "1_1") (pintype "passive"))
      (node (ref "R13") (pin "2") (pinfunction "2_2") (pintype "passive"))
      (node (ref "X1") (pin "2") (pinfunction "ADC_2") (pintype "passive"))
    )
    (net (code "3") (name "ADDR1") (class "Default")
      (node (ref "R2") (pin "2") (pinfunction "2_2") (pintype "passive"))
      (node (ref "U4") (pin "18") (pinfunction "ADDR_18") (pintype "bidirectional"))
    )
    (net (code "4") (name "CA1-1") (class "Default")
      (node (ref "C1-1") (pin "C") (pinfunction "C_C") (pintype "passive"))
      (node (ref "C1-2") (pin "C") (pinfunction "C_C") (pintype "passive"))
      (node (ref "C1-3") (pin "C") (pinfunction "C_C") (pintype "passive"))
      (node (ref "C1-4") (pin "C") (pinfunction "C_C") (pintype "passive"))
      (node (ref "C1-5") (pin "C") (pinfunction "C_C") (pintype "passive"))
      (node (ref "C1-6") (pin "C") (pinfunction "C_C") (pintype "passive"))
      (node (ref "C1-7") (pin "C") (pinfunction "C_C") (pintype "passive"))
      (node (ref "C1-8") (pin "C") (pinfunction "C_C") (pintype "passive"))
      (node (ref "C2-1") (pin "A") (pinfunction "A_A") (pintype "passive"))
      (node (ref "C3-1") (pin "A") (pinfunction "A_A") (pintype "passive"))
      (node (ref "C4-1") (pin "A") (pinfunction "A_A") (pintype "passive"))
      (node (ref "C5-1") (pin "A") (pinfunction "A_A") (pintype "passive"))
      (node (ref "C6-1") (pin "A") (pinfunction "A_A") (pintype "passive"))
      (node (ref "C7-1") (pin "A") (pinfunction "A_A") (pintype "passive"))
      (node (ref "C8-1") (pin "A") (pinfunction "A_A") (pintype "passive"))
      (node (ref "C9-1") (pin "A") (pinfunction "A_A") (pintype "passive"))
      (node (ref "U4") (pin "21") (pinfunction "CA1_21") (pintype "bidirectional"))
    )
    (net (code "5") (name "CA1-2") (class "Default")
      (node (ref "C1-17") (pin "C") (pinfunction "C_C") (pintype "passive"))
      (node (ref "C1-18") (pin "C") (pinfunction "C_C") (pintype "passive"))
      (node (ref "C1-19") (pin "C") (pinfunction "C_C") (pintype "passive"))
      (node (ref "C1-20") (pin "C") (pinfunction "C_C") (pintype "passive"))
      (node (ref "C1-21") (pin "C") (pinfunction "C_C") (pintype "passive"))
      (node (ref "C1-22") (pin "C") (pinfunction "C_C") (pintype "passive"))
      (node (ref "C1-23") (pin "C") (pinfunction "C_C") (pintype "passive"))
      (node (ref "C1-24") (pin "C") (pinfunction "C_C") (pintype "passive"))
      (node (ref "C2-17") (pin "A") (pinfunction "A_A") (pintype "passive"))
      (node (ref "C3-17") (pin "A") (pinfunction "A_A") (pintype "passive"))
      (node (ref "C4-17") (pin "A") (pinfunction "A_A") (pintype "passive"))
      (node (ref "C5-17") (pin "A") (pinfunction "A_A") (pintype "passive"))
      (node (ref "C6-17") (pin "A") (pinfunction "A_A") (pintype "passive"))
      (node (ref "C7-17") (pin "A") (pinfunction "A_A") (pintype "passive"))
      (node (ref "C8-17") (pin "A") (pinfunction "A_A") (pintype "passive"))
      (node (ref "C9-17") (pin "A") (pinfunction "A_A") (pintype "passive"))
      (node (ref "U2") (pin "21") (pinfunction "CA1_21") (pintype "bidirectional"))
    )
    (net (code "6") (name "CA2-1") (class "Default")
      (node (ref "C1-1") (pin "A") (pinfunction "A_A") (pintype "passive"))
      (node (ref "C2-1") (pin "C") (pinfunction "C_C") (pintype "passive"))
      (node (ref "C2-2") (pin "C") (pinfunction "C_C") (pintype "passive"))
      (node (ref "C2-3") (pin "C") (pinfunction "C_C") (pintype "passive"))
      (node (ref "C2-4") (pin "C") (pinfunction "C_C") (pintype "passive"))
      (node (ref "C2-5") (pin "C") (pinfunction "C_C") (pintype "passive"))
      (node (ref "C2-6") (pin "C") (pinfunction "C_C") (pintype "passive"))
      (node (ref "C2-7") (pin "C") (pinfunction "C_C") (pintype "passive"))
      (node (ref "C2-8") (pin "C") (pinfunction "C_C") (pintype "passive"))
      (node (ref "C3-2") (pin "A") (pinfunction "A_A") (pintype "passive"))
      (node (ref "C4-2") (pin "A") (pinfunction "A_A") (pintype "passive"))
      (node (ref "C5-2") (pin "A") (pinfunction "A_A") (pintype "passive"))
      (node (ref "C6-2") (pin "A") (pinfunction "A_A") (pintype "passive"))
      (node (ref "C7-2") (pin "A") (pinfunction "A_A") (pintype "passive"))
      (node (ref "C8-2") (pin "A") (pinfunction "A_A") (pintype "passive"))
      (node (ref "C9-2") (pin "A") (pinfunction "A_A") (pintype "passive"))
      (node (ref "U4") (pin "22") (pinfunction "CA2_22") (pintype "bidirectional"))
    )
    (net (code "7") (name "CA2-2") (class "Default")
      (node (ref "C1-17") (pin "A") (pinfunction "A_A") (pintype "passive"))
      (node (ref "C2-17") (pin "C") (pinfunction "C_C") (pintype "passive"))
      (node (ref "C2-18") (pin "C") (pinfunction "C_C") (pintype "passive"))
      (node (ref "C2-19") (pin "C") (pinfunction "C_C") (pintype "passive"))
      (node (ref "C2-20") (pin "C") (pinfunction "C_C") (pintype "passive"))
      (node (ref "C2-21") (pin "C") (pinfunction "C_C") (pintype "passive"))
      (node (ref "C2-22") (pin "C") (pinfunction "C_C") (pintype "passive"))
      (node (ref "C2-23") (pin "C") (pinfunction "C_C") (pintype "passive"))
      (node (ref "C2-24") (pin "C") (pinfunction "C_C") (pintype "passive"))
      (node (ref "C3-18") (pin "A") (pinfunction "A_A") (pintype "passive"))
      (node (ref "C4-18") (pin "A") (pinfunction "A_A") (pintype "passive"))
      (node (ref "C5-18") (pin "A") (pinfunction "A_A") (pintype "passive"))
      (node (ref "C6-18") (pin "A") (pinfunction "A_A") (pintype "passive"))
      (node (ref "C7-18") (pin "A") (pinfunction "A_A") (pintype "passive"))
      (node (ref "C8-18") (pin "A") (pinfunction "A_A") (pintype "passive"))
      (node (ref "C9-18") (pin "A") (pinfunction "A_A") (pintype "passive"))
      (node (ref "U2") (pin "22") (pinfunction "CA2_22") (pintype "bidirectional"))
    )
    (net (code "8") (name "CA3-1") (class "Default")
      (node (ref "C1-2") (pin "A") (pinfunction "A_A") (pintype "passive"))
      (node (ref "C2-2") (pin "A") (pinfunction "A_A") (pintype "passive"))
      (node (ref "C3-1") (pin "C") (pinfunction "C_C") (pintype "passive"))
      (node (ref "C3-2") (pin "C") (pinfunction "C_C") (pintype "passive"))
      (node (ref "C3-3") (pin "C") (pinfunction "C_C") (pintype "passive"))
      (node (ref "C3-4") (pin "C") (pinfunction "C_C") (pintype "passive"))
      (node (ref "C3-5") (pin "C") (pinfunction "C_C") (pintype "passive"))
      (node (ref "C3-6") (pin "C") (pinfunction "C_C") (pintype "passive"))
      (node (ref "C3-7") (pin "C") (pinfunction "C_C") (pintype "passive"))
      (node (ref "C3-8") (pin "C") (pinfunction "C_C") (pintype "passive"))
      (node (ref "C4-3") (pin "A") (pinfunction "A_A") (pintype "passive"))
      (node (ref "C5-3") (pin "A") (pinfunction "A_A") (pintype "passive"))
      (node (ref "C6-3") (pin "A") (pinfunction "A_A") (pintype "passive"))
      (node (ref "C7-3") (pin "A") (pinfunction "A_A") (pintype "passive"))
      (node (ref "C8-3") (pin "A") (pinfunction "A_A") (pintype "passive"))
      (node (ref "C9-3") (pin "A") (pinfunction "A_A") (pintype "passive"))
      (node (ref "U4") (pin "23") (pinfunction "CA3_23") (pintype "bidirectional"))
    )
    (net (code "9") (name "CA3-2") (class "Default")
      (node (ref "C1-18") (pin "A") (pinfunction "A_A") (pintype "passive"))
      (node (ref "C2-18") (pin "A") (pinfunction "A_A") (pintype "passive"))
      (node (ref "C3-17") (pin "C") (pinfunction "C_C") (pintype "passive"))
      (node (ref "C3-18") (pin "C") (pinfunction "C_C") (pintype "passive"))
      (node (ref "C3-19") (pin "C") (pinfunction "C_C") (pintype "passive"))
      (node (ref "C3-20") (pin "C") (pinfunction "C_C") (pintype "passive"))
      (node (ref "C3-21") (pin "C") (pinfunction "C_C") (pintype "passive"))
      (node (ref "C3-22") (pin "C") (pinfunction "C_C") (pintype "passive"))
      (node (ref "C3-23") (pin "C") (pinfunction "C_C") (pintype "passive"))
      (node (ref "C3-24") (pin "C") (pinfunction "C_C") (pintype "passive"))
      (node (ref "C4-19") (pin "A") (pinfunction "A_A") (pintype "passive"))
      (node (ref "C5-19") (pin "A") (pinfunction "A_A") (pintype "passive"))
      (node (ref "C6-19") (pin "A") (pinfunction "A_A") (pintype "passive"))
      (node (ref "C7-19") (pin "A") (pinfunction "A_A") (pintype "passive"))
      (node (ref "C8-19") (pin "A") (pinfunction "A_A") (pintype "passive"))
      (node (ref "C9-19") (pin "A") (pinfunction "A_A") (pintype "passive"))
      (node (ref "U2") (pin "23") (pinfunction "CA3_23") (pintype "bidirectional"))
    )
    (net (code "10") (name "CA4-1") (class "Default")
      (node (ref "C1-3") (pin "A") (pinfunction "A_A") (pintype "passive"))
      (node (ref "C2-3") (pin "A") (pinfunction "A_A") (pintype "passive"))
      (node (ref "C3-3") (pin "A") (pinfunction "A_A") (pintype "passive"))
      (node (ref "C4-1") (pin "C") (pinfunction "C_C") (pintype "passive"))
      (node (ref "C4-2") (pin "C") (pinfunction "C_C") (pintype "passive"))
      (node (ref "C4-3") (pin "C") (pinfunction "C_C") (pintype "passive"))
      (node (ref "C4-4") (pin "C") (pinfunction "C_C") (pintype "passive"))
      (node (ref "C4-5") (pin "C") (pinfunction "C_C") (pintype "passive"))
      (node (ref "C4-6") (pin "C") (pinfunction "C_C") (pintype "passive"))
      (node (ref "C4-7") (pin "C") (pinfunction "C_C") (pintype "passive"))
      (node (ref "C4-8") (pin "C") (pinfunction "C_C") (pintype "passive"))
      (node (ref "C5-4") (pin "A") (pinfunction "A_A") (pintype "passive"))
      (node (ref "C6-4") (pin "A") (pinfunction "A_A") (pintype "passive"))
      (node (ref "C7-4") (pin "A") (pinfunction "A_A") (pintype "passive"))
      (node (ref "C8-4") (pin "A") (pinfunction "A_A") (pintype "passive"))
      (node (ref "C9-4") (pin "A") (pinfunction "A_A") (pintype "passive"))
      (node (ref "U4") (pin "24") (pinfunction "CA4_24") (pintype "bidirectional"))
    )
    (net (code "11") (name "CA4-2") (class "Default")
      (node (ref "C1-19") (pin "A") (pinfunction "A_A") (pintype "passive"))
      (node (ref "C2-19") (pin "A") (pinfunction "A_A") (pintype "passive"))
      (node (ref "C3-19") (pin "A") (pinfunction "A_A") (pintype "passive"))
      (node (ref "C4-17") (pin "C") (pinfunction "C_C") (pintype "passive"))
      (node (ref "C4-18") (pin "C") (pinfunction "C_C") (pintype "passive"))
      (node (ref "C4-19") (pin "C") (pinfunction "C_C") (pintype "passive"))
      (node (ref "C4-20") (pin "C") (pinfunction "C_C") (pintype "passive"))
      (node (ref "C4-21") (pin "C") (pinfunction "C_C") (pintype "passive"))
      (node (ref "C4-22") (pin "C") (pinfunction "C_C") (pintype "passive"))
      (node (ref "C4-23") (pin "C") (pinfunction "C_C") (pintype "passive"))
      (node (ref "C4-24") (pin "C") (pinfunction "C_C") (pintype "passive"))
      (node (ref "C5-20") (pin "A") (pinfunction "A_A") (pintype "passive"))
      (node (ref "C6-20") (pin "A") (pinfunction "A_A") (pintype "passive"))
      (node (ref "C7-20") (pin "A") (pinfunction "A_A") (pintype "passive"))
      (node (ref "C8-20") (pin "A") (pinfunction "A_A") (pintype "passive"))
      (node (ref "C9-20") (pin "A") (pinfunction "A_A") (pintype "passive"))
      (node (ref "U2") (pin "24") (pinfunction "CA4_24") (pintype "bidirectional"))
    )
    (net (code "12") (name "CA5-1") (class "Default")
      (node (ref "C1-4") (pin "A") (pinfunction "A_A") (pintype "passive"))
      (node (ref "C2-4") (pin "A") (pinfunction "A_A") (pintype "passive"))
      (node (ref "C3-4") (pin "A") (pinfunction "A_A") (pintype "passive"))
      (node (ref "C4-4") (pin "A") (pinfunction "A_A") (pintype "passive"))
      (node (ref "C5-1") (pin "C") (pinfunction "C_C") (pintype "passive"))
      (node (ref "C5-2") (pin "C") (pinfunction "C_C") (pintype "passive"))
      (node (ref "C5-3") (pin "C") (pinfunction "C_C") (pintype "passive"))
      (node (ref "C5-4") (pin "C") (pinfunction "C_C") (pintype "passive"))
      (node (ref "C5-5") (pin "C") (pinfunction "C_C") (pintype "passive"))
      (node (ref "C5-6") (pin "C") (pinfunction "C_C") (pintype "passive"))
      (node (ref "C5-7") (pin "C") (pinfunction "C_C") (pintype "passive"))
      (node (ref "C5-8") (pin "C") (pinfunction "C_C") (pintype "passive"))
      (node (ref "C6-5") (pin "A") (pinfunction "A_A") (pintype "passive"))
      (node (ref "C7-5") (pin "A") (pinfunction "A_A") (pintype "passive"))
      (node (ref "C8-5") (pin "A") (pinfunction "A_A") (pintype "passive"))
      (node (ref "C9-5") (pin "A") (pinfunction "A_A") (pintype "passive"))
      (node (ref "U4") (pin "25") (pinfunction "CA5_25") (pintype "bidirectional"))
    )
    (net (code "13") (name "CA5-2") (class "Default")
      (node (ref "C1-20") (pin "A") (pinfunction "A_A") (pintype "passive"))
      (node (ref "C2-20") (pin "A") (pinfunction "A_A") (pintype "passive"))
      (node (ref "C3-20") (pin "A") (pinfunction "A_A") (pintype "passive"))
      (node (ref "C4-20") (pin "A") (pinfunction "A_A") (pintype "passive"))
      (node (ref "C5-17") (pin "C") (pinfunction "C_C") (pintype "passive"))
      (node (ref "C5-18") (pin "C") (pinfunction "C_C") (pintype "passive"))
      (node (ref "C5-19") (pin "C") (pinfunction "C_C") (pintype "passive"))
      (node (ref "C5-20") (pin "C") (pinfunction "C_C") (pintype "passive"))
      (node (ref "C5-21") (pin "C") (pinfunction "C_C") (pintype "passive"))
      (node (ref "C5-22") (pin "C") (pinfunction "C_C") (pintype "passive"))
      (node (ref "C5-23") (pin "C") (pinfunction "C_C") (pintype "passive"))
      (node (ref "C5-24") (pin "C") (pinfunction "C_C") (pintype "passive"))
      (node (ref "C6-21") (pin "A") (pinfunction "A_A") (pintype "passive"))
      (node (ref "C7-21") (pin "A") (pinfunction "A_A") (pintype "passive"))
      (node (ref "C8-21") (pin "A") (pinfunction "A_A") (pintype "passive"))
      (node (ref "C9-21") (pin "A") (pinfunction "A_A") (pintype "passive"))
      (node (ref "U2") (pin "25") (pinfunction "CA5_25") (pintype "bidirectional"))
    )
    (net (code "14") (name "CA6-1") (class "Default")
      (node (ref "C1-5") (pin "A") (pinfunction "A_A") (pintype "passive"))
      (node (ref "C2-5") (pin "A") (pinfunction "A_A") (pintype "passive"))
      (node (ref "C3-5") (pin "A") (pinfunction "A_A") (pintype "passive"))
      (node (ref "C4-5") (pin "A") (pinfunction "A_A") (pintype "passive"))
      (node (ref "C5-5") (pin "A") (pinfunction "A_A") (pintype "passive"))
      (node (ref "C6-1") (pin "C") (pinfunction "C_C") (pintype "passive"))
      (node (ref "C6-2") (pin "C") (pinfunction "C_C") (pintype "passive"))
      (node (ref "C6-3") (pin "C") (pinfunction "C_C") (pintype "passive"))
      (node (ref "C6-4") (pin "C") (pinfunction "C_C") (pintype "passive"))
      (node (ref "C6-5") (pin "C") (pinfunction "C_C") (pintype "passive"))
      (node (ref "C6-6") (pin "C") (pinfunction "C_C") (pintype "passive"))
      (node (ref "C6-7") (pin "C") (pinfunction "C_C") (pintype "passive"))
      (node (ref "C6-8") (pin "C") (pinfunction "C_C") (pintype "passive"))
      (node (ref "C7-6") (pin "A") (pinfunction "A_A") (pintype "passive"))
      (node (ref "C8-6") (pin "A") (pinfunction "A_A") (pintype "passive"))
      (node (ref "C9-6") (pin "A") (pinfunction "A_A") (pintype "passive"))
      (node (ref "U4") (pin "26") (pinfunction "CA6_26") (pintype "bidirectional"))
    )
    (net (code "15") (name "CA6-2") (class "Default")
      (node (ref "C1-21") (pin "A") (pinfunction "A_A") (pintype "passive"))
      (node (ref "C2-21") (pin "A") (pinfunction "A_A") (pintype "passive"))
      (node (ref "C3-21") (pin "A") (pinfunction "A_A") (pintype "passive"))
      (node (ref "C4-21") (pin "A") (pinfunction "A_A") (pintype "passive"))
      (node (ref "C5-21") (pin "A") (pinfunction "A_A") (pintype "passive"))
      (node (ref "C6-17") (pin "C") (pinfunction "C_C") (pintype "passive"))
      (node (ref "C6-18") (pin "C") (pinfunction "C_C") (pintype "passive"))
      (node (ref "C6-19") (pin "C") (pinfunction "C_C") (pintype "passive"))
      (node (ref "C6-20") (pin "C") (pinfunction "C_C") (pintype "passive"))
      (node (ref "C6-21") (pin "C") (pinfunction "C_C") (pintype "passive"))
      (node (ref "C6-22") (pin "C") (pinfunction "C_C") (pintype "passive"))
      (node (ref "C6-23") (pin "C") (pinfunction "C_C") (pintype "passive"))
      (node (ref "C6-24") (pin "C") (pinfunction "C_C") (pintype "passive"))
      (node (ref "C7-22") (pin "A") (pinfunction "A_A") (pintype "passive"))
      (node (ref "C8-22") (pin "A") (pinfunction "A_A") (pintype "passive"))
      (node (ref "C9-22") (pin "A") (pinfunction "A_A") (pintype "passive"))
      (node (ref "U2") (pin "26") (pinfunction "CA6_26") (pintype "bidirectional"))
    )
    (net (code "16") (name "CA7-1") (class "Default")
      (node (ref "C1-6") (pin "A") (pinfunction "A_A") (pintype "passive"))
      (node (ref "C2-6") (pin "A") (pinfunction "A_A") (pintype "passive"))
      (node (ref "C3-6") (pin "A") (pinfunction "A_A") (pintype "passive"))
      (node (ref "C4-6") (pin "A") (pinfunction "A_A") (pintype "passive"))
      (node (ref "C5-6") (pin "A") (pinfunction "A_A") (pintype "passive"))
      (node (ref "C6-6") (pin "A") (pinfunction "A_A") (pintype "passive"))
      (node (ref "C7-1") (pin "C") (pinfunction "C_C") (pintype "passive"))
      (node (ref "C7-2") (pin "C") (pinfunction "C_C") (pintype "passive"))
      (node (ref "C7-3") (pin "C") (pinfunction "C_C") (pintype "passive"))
      (node (ref "C7-4") (pin "C") (pinfunction "C_C") (pintype "passive"))
      (node (ref "C7-5") (pin "C") (pinfunction "C_C") (pintype "passive"))
      (node (ref "C7-6") (pin "C") (pinfunction "C_C") (pintype "passive"))
      (node (ref "C7-7") (pin "C") (pinfunction "C_C") (pintype "passive"))
      (node (ref "C7-8") (pin "C") (pinfunction "C_C") (pintype "passive"))
      (node (ref "C8-7") (pin "A") (pinfunction "A_A") (pintype "passive"))
      (node (ref "C9-7") (pin "A") (pinfunction "A_A") (pintype "passive"))
      (node (ref "U4") (pin "27") (pinfunction "CA7_27") (pintype "bidirectional"))
    )
    (net (code "17") (name "CA7-2") (class "Default")
      (node (ref "C1-22") (pin "A") (pinfunction "A_A") (pintype "passive"))
      (node (ref "C2-22") (pin "A") (pinfunction "A_A") (pintype "passive"))
      (node (ref "C3-22") (pin "A") (pinfunction "A_A") (pintype "passive"))
      (node (ref "C4-22") (pin "A") (pinfunction "A_A") (pintype "passive"))
      (node (ref "C5-22") (pin "A") (pinfunction "A_A") (pintype "passive"))
      (node (ref "C6-22") (pin "A") (pinfunction "A_A") (pintype "passive"))
      (node (ref "C7-17") (pin "C") (pinfunction "C_C") (pintype "passive"))
      (node (ref "C7-18") (pin "C") (pinfunction "C_C") (pintype "passive"))
      (node (ref "C7-19") (pin "C") (pinfunction "C_C") (pintype "passive"))
      (node (ref "C7-20") (pin "C") (pinfunction "C_C") (pintype "passive"))
      (node (ref "C7-21") (pin "C") (pinfunction "C_C") (pintype "passive"))
      (node (ref "C7-22") (pin "C") (pinfunction "C_C") (pintype "passive"))
      (node (ref "C7-23") (pin "C") (pinfunction "C_C") (pintype "passive"))
      (node (ref "C7-24") (pin "C") (pinfunction "C_C") (pintype "passive"))
      (node (ref "C8-23") (pin "A") (pinfunction "A_A") (pintype "passive"))
      (node (ref "C9-23") (pin "A") (pinfunction "A_A") (pintype "passive"))
      (node (ref "U2") (pin "27") (pinfunction "CA7_27") (pintype "bidirectional"))
    )
    (net (code "18") (name "CA8-1") (class "Default")
      (node (ref "C1-7") (pin "A") (pinfunction "A_A") (pintype "passive"))
      (node (ref "C2-7") (pin "A") (pinfunction "A_A") (pintype "passive"))
      (node (ref "C3-7") (pin "A") (pinfunction "A_A") (pintype "passive"))
      (node (ref "C4-7") (pin "A") (pinfunction "A_A") (pintype "passive"))
      (node (ref "C5-7") (pin "A") (pinfunction "A_A") (pintype "passive"))
      (node (ref "C6-7") (pin "A") (pinfunction "A_A") (pintype "passive"))
      (node (ref "C7-7") (pin "A") (pinfunction "A_A") (pintype "passive"))
      (node (ref "C8-1") (pin "C") (pinfunction "C_C") (pintype "passive"))
      (node (ref "C8-2") (pin "C") (pinfunction "C_C") (pintype "passive"))
      (node (ref "C8-3") (pin "C") (pinfunction "C_C") (pintype "passive"))
      (node (ref "C8-4") (pin "C") (pinfunction "C_C") (pintype "passive"))
      (node (ref "C8-5") (pin "C") (pinfunction "C_C") (pintype "passive"))
      (node (ref "C8-6") (pin "C") (pinfunction "C_C") (pintype "passive"))
      (node (ref "C8-7") (pin "C") (pinfunction "C_C") (pintype "passive"))
      (node (ref "C8-8") (pin "C") (pinfunction "C_C") (pintype "passive"))
      (node (ref "C9-8") (pin "A") (pinfunction "A_A") (pintype "passive"))
      (node (ref "U4") (pin "28") (pinfunction "CA8_28") (pintype "bidirectional"))
    )
    (net (code "19") (name "CA8-2") (class "Default")
      (node (ref "C1-23") (pin "A") (pinfunction "A_A") (pintype "passive"))
      (node (ref "C2-23") (pin "A") (pinfunction "A_A") (pintype "passive"))
      (node (ref "C3-23") (pin "A") (pinfunction "A_A") (pintype "passive"))
      (node (ref "C4-23") (pin "A") (pinfunction "A_A") (pintype "passive"))
      (node (ref "C5-23") (pin "A") (pinfunction "A_A") (pintype "passive"))
      (node (ref "C6-23") (pin "A") (pinfunction "A_A") (pintype "passive"))
      (node (ref "C7-23") (pin "A") (pinfunction "A_A") (pintype "passive"))
      (node (ref "C8-17") (pin "C") (pinfunction "C_C") (pintype "passive"))
      (node (ref "C8-18") (pin "C") (pinfunction "C_C") (pintype "passive"))
      (node (ref "C8-19") (pin "C") (pinfunction "C_C") (pintype "passive"))
      (node (ref "C8-20") (pin "C") (pinfunction "C_C") (pintype "passive"))
      (node (ref "C8-21") (pin "C") (pinfunction "C_C") (pintype "passive"))
      (node (ref "C8-22") (pin "C") (pinfunction "C_C") (pintype "passive"))
      (node (ref "C8-23") (pin "C") (pinfunction "C_C") (pintype "passive"))
      (node (ref "C8-24") (pin "C") (pinfunction "C_C") (pintype "passive"))
      (node (ref "C9-24") (pin "A") (pinfunction "A_A") (pintype "passive"))
      (node (ref "U2") (pin "28") (pinfunction "CA8_28") (pintype "bidirectional"))
    )
    (net (code "20") (name "CA9-1") (class "Default")
      (node (ref "C1-8") (pin "A") (pinfunction "A_A") (pintype "passive"))
      (node (ref "C2-8") (pin "A") (pinfunction "A_A") (pintype "passive"))
      (node (ref "C3-8") (pin "A") (pinfunction "A_A") (pintype "passive"))
      (node (ref "C4-8") (pin "A") (pinfunction "A_A") (pintype "passive"))
      (node (ref "C5-8") (pin "A") (pinfunction "A_A") (pintype "passive"))
      (node (ref "C6-8") (pin "A") (pinfunction "A_A") (pintype "passive"))
      (node (ref "C7-8") (pin "A") (pinfunction "A_A") (pintype "passive"))
      (node (ref "C8-8") (pin "A") (pinfunction "A_A") (pintype "passive"))
      (node (ref "C9-1") (pin "C") (pinfunction "C_C") (pintype "passive"))
      (node (ref "C9-2") (pin "C") (pinfunction "C_C") (pintype "passive"))
      (node (ref "C9-3") (pin "C") (pinfunction "C_C") (pintype "passive"))
      (node (ref "C9-4") (pin "C") (pinfunction "C_C") (pintype "passive"))
      (node (ref "C9-5") (pin "C") (pinfunction "C_C") (pintype "passive"))
      (node (ref "C9-6") (pin "C") (pinfunction "C_C") (pintype "passive"))
      (node (ref "C9-7") (pin "C") (pinfunction "C_C") (pintype "passive"))
      (node (ref "C9-8") (pin "C") (pinfunction "C_C") (pintype "passive"))
      (node (ref "U4") (pin "1") (pinfunction "CA9_1") (pintype "bidirectional"))
    )
    (net (code "21") (name "CA9-2") (class "Default")
      (node (ref "C1-24") (pin "A") (pinfunction "A_A") (pintype "passive"))
      (node (ref "C2-24") (pin "A") (pinfunction "A_A") (pintype "passive"))
      (node (ref "C3-24") (pin "A") (pinfunction "A_A") (pintype "passive"))
      (node (ref "C4-24") (pin "A") (pinfunction "A_A") (pintype "passive"))
      (node (ref "C5-24") (pin "A") (pinfunction "A_A") (pintype "passive"))
      (node (ref "C6-24") (pin "A") (pinfunction "A_A") (pintype "passive"))
      (node (ref "C7-24") (pin "A") (pinfunction "A_A") (pintype "passive"))
      (node (ref "C8-24") (pin "A") (pinfunction "A_A") (pintype "passive"))
      (node (ref "C9-17") (pin "C") (pinfunction "C_C") (pintype "passive"))
      (node (ref "C9-18") (pin "C") (pinfunction "C_C") (pintype "passive"))
      (node (ref "C9-19") (pin "C") (pinfunction "C_C") (pintype "passive"))
      (node (ref "C9-20") (pin "C") (pinfunction "C_C") (pintype "passive"))
      (node (ref "C9-21") (pin "C") (pinfunction "C_C") (pintype "passive"))
      (node (ref "C9-22") (pin "C") (pinfunction "C_C") (pintype "passive"))
      (node (ref "C9-23") (pin "C") (pinfunction "C_C") (pintype "passive"))
      (node (ref "C9-24") (pin "C") (pinfunction "C_C") (pintype "passive"))
      (node (ref "U2") (pin "1") (pinfunction "CA9_1") (pintype "bidirectional"))
    )
    (net (code "22") (name "CB1-1") (class "Default")
      (node (ref "C1-10") (pin "C") (pinfunction "C_C") (pintype "passive"))
      (node (ref "C1-11") (pin "C") (pinfunction "C_C") (pintype "passive"))
      (node (ref "C1-12") (pin "C") (pinfunction "C_C") (pintype "passive"))
      (node (ref "C1-13") (pin "C") (pinfunction "C_C") (pintype "passive"))
      (node (ref "C1-14") (pin "C") (pinfunction "C_C") (pintype "passive"))
      (node (ref "C1-15") (pin "C") (pinfunction "C_C") (pintype "passive"))
      (node (ref "C1-16") (pin "C") (pinfunction "C_C") (pintype "passive"))
      (node (ref "C1-9") (pin "C") (pinfunction "C_C") (pintype "passive"))
      (node (ref "C2-9") (pin "A") (pinfunction "A_A") (pintype "passive"))
      (node (ref "C3-9") (pin "A") (pinfunction "A_A") (pintype "passive"))
      (node (ref "C4-9") (pin "A") (pinfunction "A_A") (pintype "passive"))
      (node (ref "C5-9") (pin "A") (pinfunction "A_A") (pintype "passive"))
      (node (ref "C6-9") (pin "A") (pinfunction "A_A") (pintype "passive"))
      (node (ref "C7-9") (pin "A") (pinfunction "A_A") (pintype "passive"))
      (node (ref "C8-9") (pin "A") (pinfunction "A_A") (pintype "passive"))
      (node (ref "C9-9") (pin "A") (pinfunction "A_A") (pintype "passive"))
      (node (ref "U4") (pin "7") (pinfunction "CB1_7") (pintype "bidirectional"))
    )
    (net (code "23") (name "CB1-2") (class "Default")
      (node (ref "C1-25") (pin "C") (pinfunction "C_C") (pintype "passive"))
      (node (ref "C1-26") (pin "C") (pinfunction "C_C") (pintype "passive"))
      (node (ref "C1-27") (pin "C") (pinfunction "C_C") (pintype "passive"))
      (node (ref "C1-28") (pin "C") (pinfunction "C_C") (pintype "passive"))
      (node (ref "C1-29") (pin "C") (pinfunction "C_C") (pintype "passive"))
      (node (ref "C1-30") (pin "C") (pinfunction "C_C") (pintype "passive"))
      (node (ref "C1-31") (pin "C") (pinfunction "C_C") (pintype "passive"))
      (node (ref "C1-32") (pin "C") (pinfunction "C_C") (pintype "passive"))
      (node (ref "C2-25") (pin "A") (pinfunction "A_A") (pintype "passive"))
      (node (ref "C3-25") (pin "A") (pinfunction "A_A") (pintype "passive"))
      (node (ref "C4-25") (pin "A") (pinfunction "A_A") (pintype "passive"))
      (node (ref "C5-25") (pin "A") (pinfunction "A_A") (pintype "passive"))
      (node (ref "C6-25") (pin "A") (pinfunction "A_A") (pintype "passive"))
      (node (ref "C7-25") (pin "A") (pinfunction "A_A") (pintype "passive"))
      (node (ref "C8-25") (pin "A") (pinfunction "A_A") (pintype "passive"))
      (node (ref "C9-25") (pin "A") (pinfunction "A_A") (pintype "passive"))
      (node (ref "U2") (pin "7") (pinfunction "CB1_7") (pintype "bidirectional"))
    )
    (net (code "24") (name "CB2-1") (class "Default")
      (node (ref "C1-9") (pin "A") (pinfunction "A_A") (pintype "passive"))
      (node (ref "C2-10") (pin "C") (pinfunction "C_C") (pintype "passive"))
      (node (ref "C2-11") (pin "C") (pinfunction "C_C") (pintype "passive"))
      (node (ref "C2-12") (pin "C") (pinfunction "C_C") (pintype "passive"))
      (node (ref "C2-13") (pin "C") (pinfunction "C_C") (pintype "passive"))
      (node (ref "C2-14") (pin "C") (pinfunction "C_C") (pintype "passive"))
      (node (ref "C2-15") (pin "C") (pinfunction "C_C") (pintype "passive"))
      (node (ref "C2-16") (pin "C") (pinfunction "C_C") (pintype "passive"))
      (node (ref "C2-9") (pin "C") (pinfunction "C_C") (pintype "passive"))
      (node (ref "C3-10") (pin "A") (pinfunction "A_A") (pintype "passive"))
      (node (ref "C4-10") (pin "A") (pinfunction "A_A") (pintype "passive"))
      (node (ref "C5-10") (pin "A") (pinfunction "A_A") (pintype "passive"))
      (node (ref "C6-10") (pin "A") (pinfunction "A_A") (pintype "passive"))
      (node (ref "C7-10") (pin "A") (pinfunction "A_A") (pintype "passive"))
      (node (ref "C8-10") (pin "A") (pinfunction "A_A") (pintype "passive"))
      (node (ref "C9-10") (pin "A") (pinfunction "A_A") (pintype "passive"))
      (node (ref "U4") (pin "8") (pinfunction "CB2_8") (pintype "bidirectional"))
    )
    (net (code "25") (name "CB2-2") (class "Default")
      (node (ref "C1-25") (pin "A") (pinfunction "A_A") (pintype "passive"))
      (node (ref "C2-25") (pin "C") (pinfunction "C_C") (pintype "passive"))
      (node (ref "C2-26") (pin "C") (pinfunction "C_C") (pintype "passive"))
      (node (ref "C2-27") (pin "C") (pinfunction "C_C") (pintype "passive"))
      (node (ref "C2-28") (pin "C") (pinfunction "C_C") (pintype "passive"))
      (node (ref "C2-29") (pin "C") (pinfunction "C_C") (pintype "passive"))
      (node (ref "C2-30") (pin "C") (pinfunction "C_C") (pintype "passive"))
      (node (ref "C2-31") (pin "C") (pinfunction "C_C") (pintype "passive"))
      (node (ref "C2-32") (pin "C") (pinfunction "C_C") (pintype "passive"))
      (node (ref "C3-26") (pin "A") (pinfunction "A_A") (pintype "passive"))
      (node (ref "C4-26") (pin "A") (pinfunction "A_A") (pintype "passive"))
      (node (ref "C5-26") (pin "A") (pinfunction "A_A") (pintype "passive"))
      (node (ref "C6-26") (pin "A") (pinfunction "A_A") (pintype "passive"))
      (node (ref "C7-26") (pin "A") (pinfunction "A_A") (pintype "passive"))
      (node (ref "C8-26") (pin "A") (pinfunction "A_A") (pintype "passive"))
      (node (ref "C9-26") (pin "A") (pinfunction "A_A") (pintype "passive"))
      (node (ref "U2") (pin "8") (pinfunction "CB2_8") (pintype "bidirectional"))
    )
    (net (code "26") (name "CB3-1") (class "Default")
      (node (ref "C1-10") (pin "A") (pinfunction "A_A") (pintype "passive"))
      (node (ref "C2-10") (pin "A") (pinfunction "A_A") (pintype "passive"))
      (node (ref "C3-10") (pin "C") (pinfunction "C_C") (pintype "passive"))
      (node (ref "C3-11") (pin "C") (pinfunction "C_C") (pintype "passive"))
      (node (ref "C3-12") (pin "C") (pinfunction "C_C") (pintype "passive"))
      (node (ref "C3-13") (pin "C") (pinfunction "C_C") (pintype "passive"))
      (node (ref "C3-14") (pin "C") (pinfunction "C_C") (pintype "passive"))
      (node (ref "C3-15") (pin "C") (pinfunction "C_C") (pintype "passive"))
      (node (ref "C3-16") (pin "C") (pinfunction "C_C") (pintype "passive"))
      (node (ref "C3-9") (pin "C") (pinfunction "C_C") (pintype "passive"))
      (node (ref "C4-11") (pin "A") (pinfunction "A_A") (pintype "passive"))
      (node (ref "C5-11") (pin "A") (pinfunction "A_A") (pintype "passive"))
      (node (ref "C6-11") (pin "A") (pinfunction "A_A") (pintype "passive"))
      (node (ref "C7-11") (pin "A") (pinfunction "A_A") (pintype "passive"))
      (node (ref "C8-11") (pin "A") (pinfunction "A_A") (pintype "passive"))
      (node (ref "C9-11") (pin "A") (pinfunction "A_A") (pintype "passive"))
      (node (ref "U4") (pin "9") (pinfunction "CB3_9") (pintype "bidirectional"))
    )
    (net (code "27") (name "CB3-2") (class "Default")
      (node (ref "C1-26") (pin "A") (pinfunction "A_A") (pintype "passive"))
      (node (ref "C2-26") (pin "A") (pinfunction "A_A") (pintype "passive"))
      (node (ref "C3-25") (pin "C") (pinfunction "C_C") (pintype "passive"))
      (node (ref "C3-26") (pin "C") (pinfunction "C_C") (pintype "passive"))
      (node (ref "C3-27") (pin "C") (pinfunction "C_C") (pintype "passive"))
      (node (ref "C3-28") (pin "C") (pinfunction "C_C") (pintype "passive"))
      (node (ref "C3-29") (pin "C") (pinfunction "C_C") (pintype "passive"))
      (node (ref "C3-30") (pin "C") (pinfunction "C_C") (pintype "passive"))
      (node (ref "C3-31") (pin "C") (pinfunction "C_C") (pintype "passive"))
      (node (ref "C3-32") (pin "C") (pinfunction "C_C") (pintype "passive"))
      (node (ref "C4-27") (pin "A") (pinfunction "A_A") (pintype "passive"))
      (node (ref "C5-27") (pin "A") (pinfunction "A_A") (pintype "passive"))
      (node (ref "C6-27") (pin "A") (pinfunction "A_A") (pintype "passive"))
      (node (ref "C7-27") (pin "A") (pinfunction "A_A") (pintype "passive"))
      (node (ref "C8-27") (pin "A") (pinfunction "A_A") (pintype "passive"))
      (node (ref "C9-27") (pin "A") (pinfunction "A_A") (pintype "passive"))
      (node (ref "U2") (pin "9") (pinfunction "CB3_9") (pintype "bidirectional"))
    )
    (net (code "28") (name "CB4-1") (class "Default")
      (node (ref "C1-11") (pin "A") (pinfunction "A_A") (pintype "passive"))
      (node (ref "C2-11") (pin "A") (pinfunction "A_A") (pintype "passive"))
      (node (ref "C3-11") (pin "A") (pinfunction "A_A") (pintype "passive"))
      (node (ref "C4-10") (pin "C") (pinfunction "C_C") (pintype "passive"))
      (node (ref "C4-11") (pin "C") (pinfunction "C_C") (pintype "passive"))
      (node (ref "C4-12") (pin "C") (pinfunction "C_C") (pintype "passive"))
      (node (ref "C4-13") (pin "C") (pinfunction "C_C") (pintype "passive"))
      (node (ref "C4-14") (pin "C") (pinfunction "C_C") (pintype "passive"))
      (node (ref "C4-15") (pin "C") (pinfunction "C_C") (pintype "passive"))
      (node (ref "C4-16") (pin "C") (pinfunction "C_C") (pintype "passive"))
      (node (ref "C4-9") (pin "C") (pinfunction "C_C") (pintype "passive"))
      (node (ref "C5-12") (pin "A") (pinfunction "A_A") (pintype "passive"))
      (node (ref "C6-12") (pin "A") (pinfunction "A_A") (pintype "passive"))
      (node (ref "C7-12") (pin "A") (pinfunction "A_A") (pintype "passive"))
      (node (ref "C8-12") (pin "A") (pinfunction "A_A") (pintype "passive"))
      (node (ref "C9-12") (pin "A") (pinfunction "A_A") (pintype "passive"))
      (node (ref "U4") (pin "10") (pinfunction "CB4_10") (pintype "bidirectional"))
    )
    (net (code "29") (name "CB4-2") (class "Default")
      (node (ref "C1-27") (pin "A") (pinfunction "A_A") (pintype "passive"))
      (node (ref "C2-27") (pin "A") (pinfunction "A_A") (pintype "passive"))
      (node (ref "C3-27") (pin "A") (pinfunction "A_A") (pintype "passive"))
      (node (ref "C4-25") (pin "C") (pinfunction "C_C") (pintype "passive"))
      (node (ref "C4-26") (pin "C") (pinfunction "C_C") (pintype "passive"))
      (node (ref "C4-27") (pin "C") (pinfunction "C_C") (pintype "passive"))
      (node (ref "C4-28") (pin "C") (pinfunction "C_C") (pintype "passive"))
      (node (ref "C4-29") (pin "C") (pinfunction "C_C") (pintype "passive"))
      (node (ref "C4-30") (pin "C") (pinfunction "C_C") (pintype "passive"))
      (node (ref "C4-31") (pin "C") (pinfunction "C_C") (pintype "passive"))
      (node (ref "C4-32") (pin "C") (pinfunction "C_C") (pintype "passive"))
      (node (ref "C5-28") (pin "A") (pinfunction "A_A") (pintype "passive"))
      (node (ref "C6-28") (pin "A") (pinfunction "A_A") (pintype "passive"))
      (node (ref "C7-28") (pin "A") (pinfunction "A_A") (pintype "passive"))
      (node (ref "C8-28") (pin "A") (pinfunction "A_A") (pintype "passive"))
      (node (ref "C9-28") (pin "A") (pinfunction "A_A") (pintype "passive"))
      (node (ref "U2") (pin "10") (pinfunction "CB4_10") (pintype "bidirectional"))
    )
    (net (code "30") (name "CB5-1") (class "Default")
      (node (ref "C1-12") (pin "A") (pinfunction "A_A") (pintype "passive"))
      (node (ref "C2-12") (pin "A") (pinfunction "A_A") (pintype "passive"))
      (node (ref "C3-12") (pin "A") (pinfunction "A_A") (pintype "passive"))
      (node (ref "C4-12") (pin "A") (pinfunction "A_A") (pintype "passive"))
      (node (ref "C5-10") (pin "C") (pinfunction "C_C") (pintype "passive"))
      (node (ref "C5-11") (pin "C") (pinfunction "C_C") (pintype "passive"))
      (node (ref "C5-12") (pin "C") (pinfunction "C_C") (pintype "passive"))
      (node (ref "C5-13") (pin "C") (pinfunction "C_C") (pintype "passive"))
      (node (ref "C5-14") (pin "C") (pinfunction "C_C") (pintype "passive"))
      (node (ref "C5-15") (pin "C") (pinfunction "C_C") (pintype "passive"))
      (node (ref "C5-16") (pin "C") (pinfunction "C_C") (pintype "passive"))
      (node (ref "C5-9") (pin "C") (pinfunction "C_C") (pintype "passive"))
      (node (ref "C6-13") (pin "A") (pinfunction "A_A") (pintype "passive"))
      (node (ref "C7-13") (pin "A") (pinfunction "A_A") (pintype "passive"))
      (node (ref "C8-13") (pin "A") (pinfunction "A_A") (pintype "passive"))
      (node (ref "C9-13") (pin "A") (pinfunction "A_A") (pintype "passive"))
      (node (ref "U4") (pin "11") (pinfunction "CB5_11") (pintype "bidirectional"))
    )
    (net (code "31") (name "CB5-2") (class "Default")
      (node (ref "C1-28") (pin "A") (pinfunction "A_A") (pintype "passive"))
      (node (ref "C2-28") (pin "A") (pinfunction "A_A") (pintype "passive"))
      (node (ref "C3-28") (pin "A") (pinfunction "A_A") (pintype "passive"))
      (node (ref "C4-28") (pin "A") (pinfunction "A_A") (pintype "passive"))
      (node (ref "C5-25") (pin "C") (pinfunction "C_C") (pintype "passive"))
      (node (ref "C5-26") (pin "C") (pinfunction "C_C") (pintype "passive"))
      (node (ref "C5-27") (pin "C") (pinfunction "C_C") (pintype "passive"))
      (node (ref "C5-28") (pin "C") (pinfunction "C_C") (pintype "passive"))
      (node (ref "C5-29") (pin "C") (pinfunction "C_C") (pintype "passive"))
      (node (ref "C5-30") (pin "C") (pinfunction "C_C") (pintype "passive"))
      (node (ref "C5-31") (pin "C") (pinfunction "C_C") (pintype "passive"))
      (node (ref "C5-32") (pin "C") (pinfunction "C_C") (pintype "passive"))
      (node (ref "C6-29") (pin "A") (pinfunction "A_A") (pintype "passive"))
      (node (ref "C7-29") (pin "A") (pinfunction "A_A") (pintype "passive"))
      (node (ref "C8-29") (pin "A") (pinfunction "A_A") (pintype "passive"))
      (node (ref "C9-29") (pin "A") (pinfunction "A_A") (pintype "passive"))
      (node (ref "U2") (pin "11") (pinfunction "CB5_11") (pintype "bidirectional"))
    )
    (net (code "32") (name "CB6-1") (class "Default")
      (node (ref "C1-13") (pin "A") (pinfunction "A_A") (pintype "passive"))
      (node (ref "C2-13") (pin "A") (pinfunction "A_A") (pintype "passive"))
      (node (ref "C3-13") (pin "A") (pinfunction "A_A") (pintype "passive"))
      (node (ref "C4-13") (pin "A") (pinfunction "A_A") (pintype "passive"))
      (node (ref "C5-13") (pin "A") (pinfunction "A_A") (pintype "passive"))
      (node (ref "C6-10") (pin "C") (pinfunction "C_C") (pintype "passive"))
      (node (ref "C6-11") (pin "C") (pinfunction "C_C") (pintype "passive"))
      (node (ref "C6-12") (pin "C") (pinfunction "C_C") (pintype "passive"))
      (node (ref "C6-13") (pin "C") (pinfunction "C_C") (pintype "passive"))
      (node (ref "C6-14") (pin "C") (pinfunction "C_C") (pintype "passive"))
      (node (ref "C6-15") (pin "C") (pinfunction "C_C") (pintype "passive"))
      (node (ref "C6-16") (pin "C") (pinfunction "C_C") (pintype "passive"))
      (node (ref "C6-9") (pin "C") (pinfunction "C_C") (pintype "passive"))
      (node (ref "C7-14") (pin "A") (pinfunction "A_A") (pintype "passive"))
      (node (ref "C8-14") (pin "A") (pinfunction "A_A") (pintype "passive"))
      (node (ref "C9-14") (pin "A") (pinfunction "A_A") (pintype "passive"))
      (node (ref "U4") (pin "12") (pinfunction "CB6_12") (pintype "bidirectional"))
    )
    (net (code "33") (name "CB6-2") (class "Default")
      (node (ref "C1-29") (pin "A") (pinfunction "A_A") (pintype "passive"))
      (node (ref "C2-29") (pin "A") (pinfunction "A_A") (pintype "passive"))
      (node (ref "C3-29") (pin "A") (pinfunction "A_A") (pintype "passive"))
      (node (ref "C4-29") (pin "A") (pinfunction "A_A") (pintype "passive"))
      (node (ref "C5-29") (pin "A") (pinfunction "A_A") (pintype "passive"))
      (node (ref "C6-25") (pin "C") (pinfunction "C_C") (pintype "passive"))
      (node (ref "C6-26") (pin "C") (pinfunction "C_C") (pintype "passive"))
      (node (ref "C6-27") (pin "C") (pinfunction "C_C") (pintype "passive"))
      (node (ref "C6-28") (pin "C") (pinfunction "C_C") (pintype "passive"))
      (node (ref "C6-29") (pin "C") (pinfunction "C_C") (pintype "passive"))
      (node (ref "C6-30") (pin "C") (pinfunction "C_C") (pintype "passive"))
      (node (ref "C6-31") (pin "C") (pinfunction "C_C") (pintype "passive"))
      (node (ref "C6-32") (pin "C") (pinfunction "C_C") (pintype "passive"))
      (node (ref "C7-30") (pin "A") (pinfunction "A_A") (pintype "passive"))
      (node (ref "C8-30") (pin "A") (pinfunction "A_A") (pintype "passive"))
      (node (ref "C9-30") (pin "A") (pinfunction "A_A") (pintype "passive"))
      (node (ref "U2") (pin "12") (pinfunction "CB6_12") (pintype "bidirectional"))
    )
    (net (code "34") (name "CB7-1") (class "Default")
      (node (ref "C1-14") (pin "A") (pinfunction "A_A") (pintype "passive"))
      (node (ref "C2-14") (pin "A") (pinfunction "A_A") (pintype "passive"))
      (node (ref "C3-14") (pin "A") (pinfunction "A_A") (pintype "passive"))
      (node (ref "C4-14") (pin "A") (pinfunction "A_A") (pintype "passive"))
      (node (ref "C5-14") (pin "A") (pinfunction "A_A") (pintype "passive"))
      (node (ref "C6-14") (pin "A") (pinfunction "A_A") (pintype "passive"))
      (node (ref "C7-10") (pin "C") (pinfunction "C_C") (pintype "passive"))
      (node (ref "C7-11") (pin "C") (pinfunction "C_C") (pintype "passive"))
      (node (ref "C7-12") (pin "C") (pinfunction "C_C") (pintype "passive"))
      (node (ref "C7-13") (pin "C") (pinfunction "C_C") (pintype "passive"))
      (node (ref "C7-14") (pin "C") (pinfunction "C_C") (pintype "passive"))
      (node (ref "C7-15") (pin "C") (pinfunction "C_C") (pintype "passive"))
      (node (ref "C7-16") (pin "C") (pinfunction "C_C") (pintype "passive"))
      (node (ref "C7-9") (pin "C") (pinfunction "C_C") (pintype "passive"))
      (node (ref "C8-15") (pin "A") (pinfunction "A_A") (pintype "passive"))
      (node (ref "C9-15") (pin "A") (pinfunction "A_A") (pintype "passive"))
      (node (ref "U4") (pin "13") (pinfunction "CB7_13") (pintype "bidirectional"))
    )
    (net (code "35") (name "CB7-2") (class "Default")
      (node (ref "C1-30") (pin "A") (pinfunction "A_A") (pintype "passive"))
      (node (ref "C2-30") (pin "A") (pinfunction "A_A") (pintype "passive"))
      (node (ref "C3-30") (pin "A") (pinfunction "A_A") (pintype "passive"))
      (node (ref "C4-30") (pin "A") (pinfunction "A_A") (pintype "passive"))
      (node (ref "C5-30") (pin "A") (pinfunction "A_A") (pintype "passive"))
      (node (ref "C6-30") (pin "A") (pinfunction "A_A") (pintype "passive"))
      (node (ref "C7-25") (pin "C") (pinfunction "C_C") (pintype "passive"))
      (node (ref "C7-26") (pin "C") (pinfunction "C_C") (pintype "passive"))
      (node (ref "C7-27") (pin "C") (pinfunction "C_C") (pintype "passive"))
      (node (ref "C7-28") (pin "C") (pinfunction "C_C") (pintype "passive"))
      (node (ref "C7-29") (pin "C") (pinfunction "C_C") (pintype "passive"))
      (node (ref "C7-30") (pin "C") (pinfunction "C_C") (pintype "passive"))
      (node (ref "C7-31") (pin "C") (pinfunction "C_C") (pintype "passive"))
      (node (ref "C7-32") (pin "C") (pinfunction "C_C") (pintype "passive"))
      (node (ref "C8-31") (pin "A") (pinfunction "A_A") (pintype "passive"))
      (node (ref "C9-31") (pin "A") (pinfunction "A_A") (pintype "passive"))
      (node (ref "U2") (pin "13") (pinfunction "CB7_13") (pintype "bidirectional"))
    )
    (net (code "36") (name "CB8-1") (class "Default")
      (node (ref "C1-15") (pin "A") (pinfunction "A_A") (pintype "passive"))
      (node (ref "C2-15") (pin "A") (pinfunction "A_A") (pintype "passive"))
      (node (ref "C3-15") (pin "A") (pinfunction "A_A") (pintype "passive"))
      (node (ref "C4-15") (pin "A") (pinfunction "A_A") (pintype "passive"))
      (node (ref "C5-15") (pin "A") (pinfunction "A_A") (pintype "passive"))
      (node (ref "C6-15") (pin "A") (pinfunction "A_A") (pintype "passive"))
      (node (ref "C7-15") (pin "A") (pinfunction "A_A") (pintype "passive"))
      (node (ref "C8-10") (pin "C") (pinfunction "C_C") (pintype "passive"))
      (node (ref "C8-11") (pin "C") (pinfunction "C_C") (pintype "passive"))
      (node (ref "C8-12") (pin "C") (pinfunction "C_C") (pintype "passive"))
      (node (ref "C8-13") (pin "C") (pinfunction "C_C") (pintype "passive"))
      (node (ref "C8-14") (pin "C") (pinfunction "C_C") (pintype "passive"))
      (node (ref "C8-15") (pin "C") (pinfunction "C_C") (pintype "passive"))
      (node (ref "C8-16") (pin "C") (pinfunction "C_C") (pintype "passive"))
      (node (ref "C8-9") (pin "C") (pinfunction "C_C") (pintype "passive"))
      (node (ref "C9-16") (pin "A") (pinfunction "A_A") (pintype "passive"))
      (node (ref "U4") (pin "14") (pinfunction "CB8_14") (pintype "bidirectional"))
    )
    (net (code "37") (name "CB8-2") (class "Default")
      (node (ref "C1-31") (pin "A") (pinfunction "A_A") (pintype "passive"))
      (node (ref "C2-31") (pin "A") (pinfunction "A_A") (pintype "passive"))
      (node (ref "C3-31") (pin "A") (pinfunction "A_A") (pintype "passive"))
      (node (ref "C4-31") (pin "A") (pinfunction "A_A") (pintype "passive"))
      (node (ref "C5-31") (pin "A") (pinfunction "A_A") (pintype "passive"))
      (node (ref "C6-31") (pin "A") (pinfunction "A_A") (pintype "passive"))
      (node (ref "C7-31") (pin "A") (pinfunction "A_A") (pintype "passive"))
      (node (ref "C8-25") (pin "C") (pinfunction "C_C") (pintype "passive"))
      (node (ref "C8-26") (pin "C") (pinfunction "C_C") (pintype "passive"))
      (node (ref "C8-27") (pin "C") (pinfunction "C_C") (pintype "passive"))
      (node (ref "C8-28") (pin "C") (pinfunction "C_C") (pintype "passive"))
      (node (ref "C8-29") (pin "C") (pinfunction "C_C") (pintype "passive"))
      (node (ref "C8-30") (pin "C") (pinfunction "C_C") (pintype "passive"))
      (node (ref "C8-31") (pin "C") (pinfunction "C_C") (pintype "passive"))
      (node (ref "C8-32") (pin "C") (pinfunction "C_C") (pintype "passive"))
      (node (ref "C9-32") (pin "A") (pinfunction "A_A") (pintype "passive"))
      (node (ref "U2") (pin "14") (pinfunction "CB8_14") (pintype "bidirectional"))
    )
    (net (code "38") (name "CB9-1") (class "Default")
      (node (ref "C1-16") (pin "A") (pinfunction "A_A") (pintype "passive"))
      (node (ref "C2-16") (pin "A") (pinfunction "A_A") (pintype "passive"))
      (node (ref "C3-16") (pin "A") (pinfunction "A_A") (pintype "passive"))
      (node (ref "C4-16") (pin "A") (pinfunction "A_A") (pintype "passive"))
      (node (ref "C5-16") (pin "A") (pinfunction "A_A") (pintype "passive"))
      (node (ref "C6-16") (pin "A") (pinfunction "A_A") (pintype "passive"))
      (node (ref "C7-16") (pin "A") (pinfunction "A_A") (pintype "passive"))
      (node (ref "C8-16") (pin "A") (pinfunction "A_A") (pintype "passive"))
      (node (ref "C9-10") (pin "C") (pinfunction "C_C") (pintype "passive"))
      (node (ref "C9-11") (pin "C") (pinfunction "C_C") (pintype "passive"))
      (node (ref "C9-12") (pin "C") (pinfunction "C_C") (pintype "passive"))
      (node (ref "C9-13") (pin "C") (pinfunction "C_C") (pintype "passive"))
      (node (ref "C9-14") (pin "C") (pinfunction "C_C") (pintype "passive"))
      (node (ref "C9-15") (pin "C") (pinfunction "C_C") (pintype "passive"))
      (node (ref "C9-16") (pin "C") (pinfunction "C_C") (pintype "passive"))
      (node (ref "C9-9") (pin "C") (pinfunction "C_C") (pintype "passive"))
      (node (ref "U4") (pin "15") (pinfunction "CB9_15") (pintype "bidirectional"))
    )
    (net (code "39") (name "CB9-2") (class "Default")
      (node (ref "C1-32") (pin "A") (pinfunction "A_A") (pintype "passive"))
      (node (ref "C2-32") (pin "A") (pinfunction "A_A") (pintype "passive"))
      (node (ref "C3-32") (pin "A") (pinfunction "A_A") (pintype "passive"))
      (node (ref "C4-32") (pin "A") (pinfunction "A_A") (pintype "passive"))
      (node (ref "C5-32") (pin "A") (pinfunction "A_A") (pintype "passive"))
      (node (ref "C6-32") (pin "A") (pinfunction "A_A") (pintype "passive"))
      (node (ref "C7-32") (pin "A") (pinfunction "A_A") (pintype "passive"))
      (node (ref "C8-32") (pin "A") (pinfunction "A_A") (pintype "passive"))
      (node (ref "C9-25") (pin "C") (pinfunction "C_C") (pintype "passive"))
      (node (ref "C9-26") (pin "C") (pinfunction "C_C") (pintype "passive"))
      (node (ref "C9-27") (pin "C") (pinfunction "C_C") (pintype "passive"))
      (node (ref "C9-28") (pin "C") (pinfunction "C_C") (pintype "passive"))
      (node (ref "C9-29") (pin "C") (pinfunction "C_C") (pintype "passive"))
      (node (ref "C9-30") (pin "C") (pinfunction "C_C") (pintype "passive"))
      (node (ref "C9-31") (pin "C") (pinfunction "C_C") (pintype "passive"))
      (node (ref "C9-32") (pin "C") (pinfunction "C_C") (pintype "passive"))
      (node (ref "U2") (pin "15") (pinfunction "CB9_15") (pintype "bidirectional"))
    )
    (net (code "40") (name "CH_PD") (class "Default")
      (node (ref "R18") (pin "1") (pinfunction "1_1") (pintype "passive"))
      (node (ref "X1") (pin "3") (pinfunction "CH_PD_3") (pintype "input"))
    )
    (net (code "41") (name "GND") (class "Default")
      (node (ref "C1") (pin "2") (pinfunction "2_2") (pintype "passive"))
      (node (ref "C10") (pin "2") (pinfunction "2_2") (pintype "passive"))
      (node (ref "C111") (pin "2") (pinfunction "2_2") (pintype "passive"))
      (node (ref "C12") (pin "2") (pinfunction "2_2") (pintype "passive"))
      (node (ref "C2") (pin "2") (pinfunction "2_2") (pintype "passive"))
      (node (ref "C3") (pin "2") (pinfunction "2_2") (pintype "passive"))
      (node (ref "C4") (pin "2") (pinfunction "2_2") (pintype "passive"))
      (node (ref "C5") (pin "2") (pinfunction "2_2") (pintype "passive"))
      (node (ref "C6") (pin "2") (pinfunction "2_2") (pintype "passive"))
      (node (ref "C7") (pin "2") (pinfunction "2_2") (pintype "passive"))
      (node (ref "J3") (pin "1") (pinfunction "1_1") (pintype "power_in"))
      (node (ref "JP1") (pin "1") (pinfunction "1_1") (pintype "passive"))
      (node (ref "R1") (pin "1") (pinfunction "1_1") (pintype "passive"))
      (node (ref "R11") (pin "1") (pinfunction "1_1") (pintype "passive"))
      (node (ref "R13") (pin "1") (pinfunction "1_1") (pintype "passive"))
      (node (ref "R16") (pin "2") (pinfunction "2_2") (pintype "passive"))
      (node (ref "R2") (pin "1") (pinfunction "1_1") (pintype "passive"))
      (node (ref "R8") (pin "2") (pinfunction "2_2") (pintype "passive"))
      (node (ref "R9") (pin "1") (pinfunction "1_1") (pintype "passive"))
      (node (ref "U$14") (pin "1") (pinfunction "PAD_1") (pintype "bidirectional"))
      (node (ref "U$15") (pin "5") (pinfunction "GND_5") (pintype "bidirectional"))
      (node (ref "U$15") (pin "PAD") (pinfunction "GND_PAD") (pintype "bidirectional"))
      (node (ref "U$15") (pin "SHIELD1") (pinfunction "GND_SHIELD1") (pintype "bidirectional"))
      (node (ref "U$15") (pin "SHIELD2") (pinfunction "GND_SHIELD2") (pintype "bidirectional"))
      (node (ref "U$15") (pin "SHIELD3") (pinfunction "GND_SHIELD3") (pintype "bidirectional"))
      (node (ref "U$15") (pin "SHIELD4") (pinfunction "GND_SHIELD4") (pintype "bidirectional"))
      (node (ref "U$3") (pin "1") (pinfunction "GND_1") (pintype "bidirectional"))
      (node (ref "U$9") (pin "2") (pinfunction "GND_2") (pintype "bidirectional"))
      (node (ref "U1") (pin "2") (pinfunction "VSS_2") (pintype "power_in"))
      (node (ref "U2") (pin "29_GND") (pinfunction "GND_29_GND") (pintype "bidirectional"))
      (node (ref "U2") (pin "5") (pinfunction "GND_5") (pintype "bidirectional"))
      (node (ref "U4") (pin "29_GND") (pinfunction "GND_29_GND") (pintype "bidirectional"))
      (node (ref "U4") (pin "5") (pinfunction "GND_5") (pintype "bidirectional"))
      (node (ref "X1") (pin "9") (pinfunction "GND_9") (pintype "power_in"))
    )
    (net (code "42") (name "GPIO0") (class "Default")
      (node (ref "R20") (pin "1") (pinfunction "1_1") (pintype "passive"))
      (node (ref "U$3") (pin "6") (pinfunction "RESET_6") (pintype "bidirectional"))
      (node (ref "X1") (pin "12") (pinfunction "GPIO0_12") (pintype "bidirectional"))
    )
    (net (code "43") (name "GPIO2") (class "Default")
      (node (ref "R10") (pin "1") (pinfunction "1_1") (pintype "passive"))
      (node (ref "X1") (pin "11") (pinfunction "GPIO2_11") (pintype "bidirectional"))
    )
    (net (code "44") (name "GPIO12") (class "Default")
      (node (ref "U$6") (pin "1") (pinfunction "PAD_1") (pintype "bidirectional"))
      (node (ref "X1") (pin "6") (pinfunction "GPIO12_6") (pintype "bidirectional"))
    )
    (net (code "45") (name "GPIO13") (class "Default")
      (node (ref "U$7") (pin "1") (pinfunction "PAD_1") (pintype "bidirectional"))
      (node (ref "X1") (pin "7") (pinfunction "GPIO13_7") (pintype "bidirectional"))
    )
    (net (code "46") (name "GPIO14") (class "Default")
      (node (ref "U$5") (pin "1") (pinfunction "PAD_1") (pintype "bidirectional"))
      (node (ref "X1") (pin "5") (pinfunction "GPIO14_5") (pintype "bidirectional"))
    )
    (net (code "47") (name "GPIO15") (class "Default")
      (node (ref "R9") (pin "2") (pinfunction "2_2") (pintype "passive"))
      (node (ref "X1") (pin "10") (pinfunction "GPIO15_10") (pintype "bidirectional"))
    )
    (net (code "48") (name "GPIO16") (class "Default")
      (node (ref "U$4") (pin "1") (pinfunction "PAD_1") (pintype "bidirectional"))
      (node (ref "X1") (pin "4") (pinfunction "GPIO16_4") (pintype "bidirectional"))
    )
    (net (code "49") (name "INTB1") (class "Default")
      (node (ref "R3") (pin "1") (pinfunction "1_1") (pintype "passive"))
      (node (ref "U4") (pin "4") (pinfunction "INTB_4") (pintype "bidirectional"))
    )
    (net (code "50") (name "INTB2") (class "Default")
      (node (ref "R6") (pin "1") (pinfunction "1_1") (pintype "passive"))
      (node (ref "U2") (pin "4") (pinfunction "INTB_4") (pintype "bidirectional"))
    )
    (net (code "51") (name "Net-(LED1-PadA)") (class "Default")
      (node (ref "LED1") (pin "A") (pinfunction "A_A") (pintype "passive"))
      (node (ref "R17") (pin "2") (pinfunction "2_2") (pintype "passive"))
    )
    (net (code "52") (name "Net-(Q3-S)") (class "Default")
      (node (ref "D1") (pin "C") (pinfunction "C_C") (pintype "passive"))
      (node (ref "Q3") (pin "2") (pinfunction "S_2") (pintype "bidirectional"))
      (node (ref "S1") (pin "2") (pinfunction "2_2") (pintype "bidirectional"))
    )
    (net (code "53") (name "Net-(U1-PROG)") (class "Default")
      (node (ref "R16") (pin "1") (pinfunction "1_1") (pintype "passive"))
      (node (ref "U1") (pin "5") (pinfunction "PROG_5") (pintype "input"))
    )
    (net (code "54") (name "Net-(U1-STAT)") (class "Default")
      (node (ref "LED1") (pin "C") (pinfunction "C_C") (pintype "passive"))
      (node (ref "U1") (pin "1") (pinfunction "STAT_1") (pintype "output"))
    )
    (net (code "55") (name "Net-(U2-C_FILT)") (class "Default")
      (node (ref "C12") (pin "1") (pinfunction "1_1") (pintype "passive"))
      (node (ref "U2") (pin "16") (pinfunction "C_FILT_16") (pintype "bidirectional"))
    )
    (net (code "56") (name "Net-(U2-R_EXT)") (class "Default")
      (node (ref "R8") (pin "1") (pinfunction "1_1") (pintype "passive"))
      (node (ref "U2") (pin "6") (pinfunction "R_EXT_6") (pintype "bidirectional"))
    )
    (net (code "57") (name "Net-(U4-C_FILT)") (class "Default")
      (node (ref "C2") (pin "1") (pinfunction "1_1") (pintype "passive"))
      (node (ref "U4") (pin "16") (pinfunction "C_FILT_16") (pintype "bidirectional"))
    )
    (net (code "58") (name "Net-(U4-R_EXT)") (class "Default")
      (node (ref "R1") (pin "2") (pinfunction "2_2") (pintype "passive"))
      (node (ref "U4") (pin "6") (pinfunction "R_EXT_6") (pintype "bidirectional"))
    )
    (net (code "59") (name "RESET") (class "Default")
      (node (ref "R19") (pin "1") (pinfunction "1_1") (pintype "passive"))
      (node (ref "U$3") (pin "5") (pinfunction "GPIO0_5") (pintype "bidirectional"))
      (node (ref "X1") (pin "1") (pinfunction "RESET_1") (pintype "input"))
    )
    (net (code "60") (name "RXD") (class "Default")
      (node (ref "U$3") (pin "4") (pinfunction "RX_4") (pintype "bidirectional"))
      (node (ref "X1") (pin "15") (pinfunction "RXD_15") (pintype "input"))
    )
    (net (code "61") (name "SCL") (class "Default")
      (node (ref "J3") (pin "4") (pinfunction "4_4") (pintype "passive"))
      (node (ref "R4") (pin "1") (pinfunction "1_1") (pintype "passive"))
      (node (ref "U2") (pin "20") (pinfunction "SCL_20") (pintype "bidirectional"))
      (node (ref "U4") (pin "20") (pinfunction "SCL_20") (pintype "bidirectional"))
      (node (ref "X1") (pin "14") (pinfunction "GPIO4_14") (pintype "bidirectional"))
    )
    (net (code "62") (name "SDA") (class "Default")
      (node (ref "J3") (pin "3") (pinfunction "3_3") (pintype "passive"))
      (node (ref "R5") (pin "1") (pinfunction "1_1") (pintype "passive"))
      (node (ref "U2") (pin "19") (pinfunction "SDA_19") (pintype "bidirectional"))
      (node (ref "U4") (pin "19") (pinfunction "SDA_19") (pintype "bidirectional"))
      (node (ref "X1") (pin "13") (pinfunction "GPIO5_13") (pintype "bidirectional"))
    )
    (net (code "63") (name "SHUTDOWN1") (class "Default")
      (node (ref "R14") (pin "2") (pinfunction "2_2") (pintype "passive"))
      (node (ref "U4") (pin "3") (pinfunction "SHUTDOWN_3") (pintype "bidirectional"))
    )
    (net (code "64") (name "SHUTDOWN2") (class "Default")
      (node (ref "R7") (pin "1") (pinfunction "1_1") (pintype "passive"))
      (node (ref "U2") (pin "3") (pinfunction "SHUTDOWN_3") (pintype "bidirectional"))
    )
    (net (code "65") (name "TXD") (class "Default")
      (node (ref "U$3") (pin "3") (pinfunction "TX_3") (pintype "bidirectional"))
      (node (ref "X1") (pin "16") (pinfunction "TXD_16") (pintype "output"))
    )
    (net (code "66") (name "VCC") (class "Default")
      (node (ref "C1") (pin "1") (pinfunction "1_1") (pintype "passive"))
      (node (ref "C10") (pin "1") (pinfunction "1_1") (pintype "passive"))
      (node (ref "C111") (pin "1") (pinfunction "1_1") (pintype "passive"))
      (node (ref "C5") (pin "1") (pinfunction "1_1") (pintype "passive"))
      (node (ref "C6") (pin "1") (pinfunction "1_1") (pintype "passive"))
      (node (ref "R14") (pin "1") (pinfunction "1_1") (pintype "passive"))
      (node (ref "R3") (pin "2") (pinfunction "2_2") (pintype "passive"))
      (node (ref "R4") (pin "2") (pinfunction "2_2") (pintype "passive"))
      (node (ref "R5") (pin "2") (pinfunction "2_2") (pintype "passive"))
      (node (ref "R6") (pin "2") (pinfunction "2_2") (pintype "passive"))
      (node (ref "R7") (pin "2") (pinfunction "2_2") (pintype "passive"))
      (node (ref "S1") (pin "3") (pinfunction "3_3") (pintype "bidirectional"))
      (node (ref "U$9") (pin "1") (pinfunction "VIN_1") (pintype "bidirectional"))
      (node (ref "U$9") (pin "3") (pinfunction "EN_3") (pintype "bidirectional"))
      (node (ref "U2") (pin "18") (pinfunction "ADDR_18") (pintype "bidirectional"))
      (node (ref "U2") (pin "2") (pinfunction "VCC_2") (pintype "bidirectional"))
      (node (ref "U4") (pin "2") (pinfunction "VCC_2") (pintype "bidirectional"))
    )
    (net (code "67") (name "V_BATT") (class "Default")
      (node (ref "C7") (pin "1") (pinfunction "1_1") (pintype "passive"))
      (node (ref "JP1") (pin "2") (pinfunction "2_2") (pintype "passive"))
      (node (ref "Q3") (pin "3") (pinfunction "D_3") (pintype "bidirectional"))
      (node (ref "R12") (pin "2") (pinfunction "2_2") (pintype "passive"))
      (node (ref "U1") (pin "3") (pinfunction "VBAT_3") (pintype "power_in"))
    )
    (net (code "68") (name "V_USB") (class "Default")
      (node (ref "D1") (pin "A") (pinfunction "A_A") (pintype "passive"))
      (node (ref "Q3") (pin "1") (pinfunction "G_1") (pintype "bidirectional"))
      (node (ref "R11") (pin "2") (pinfunction "2_2") (pintype "passive"))
      (node (ref "R17") (pin "1") (pinfunction "1_1") (pintype "passive"))
      (node (ref "U$15") (pin "1") (pinfunction "VBUS_1") (pintype "bidirectional"))
      (node (ref "U1") (pin "4") (pinfunction "VIN_4") (pintype "power_in"))
    )
    (net (code "69") (name "unconnected-(S1-Pad1)") (class "Default")
      (node (ref "S1") (pin "1") (pinfunction "1_1") (pintype "bidirectional"))
    )
    (net (code "70") (name "unconnected-(U$9-NC-Pad4)") (class "Default")
      (node (ref "U$9") (pin "4") (pinfunction "NC_4") (pintype "bidirectional"))
    )
    (net (code "71") (name "unconnected-(U$15-D+-Pad3)") (class "Default")
      (node (ref "U$15") (pin "3") (pinfunction "D+_3") (pintype "bidirectional"))
    )
    (net (code "72") (name "unconnected-(U$15-D--Pad2)") (class "Default")
      (node (ref "U$15") (pin "2") (pinfunction "D-_2") (pintype "bidirectional"))
    )
    (net (code "73") (name "unconnected-(U$15-ID-Pad4)") (class "Default")
      (node (ref "U$15") (pin "4") (pinfunction "ID_4") (pintype "bidirectional"))
    )
    (net (code "74") (name "unconnected-(U2-AUDIOIN-Pad17)") (class "Default")
      (node (ref "U2") (pin "17") (pinfunction "AUDIOIN_17") (pintype "bidirectional"))
    )
    (net (code "75") (name "unconnected-(U4-AUDIOIN-Pad17)") (class "Default")
      (node (ref "U4") (pin "17") (pinfunction "AUDIOIN_17") (pintype "bidirectional"))
    )
  )
)
